# LionIRVT-PMP40182_Control.net
KiCad netlist of a schematic drawn in Altium Designer
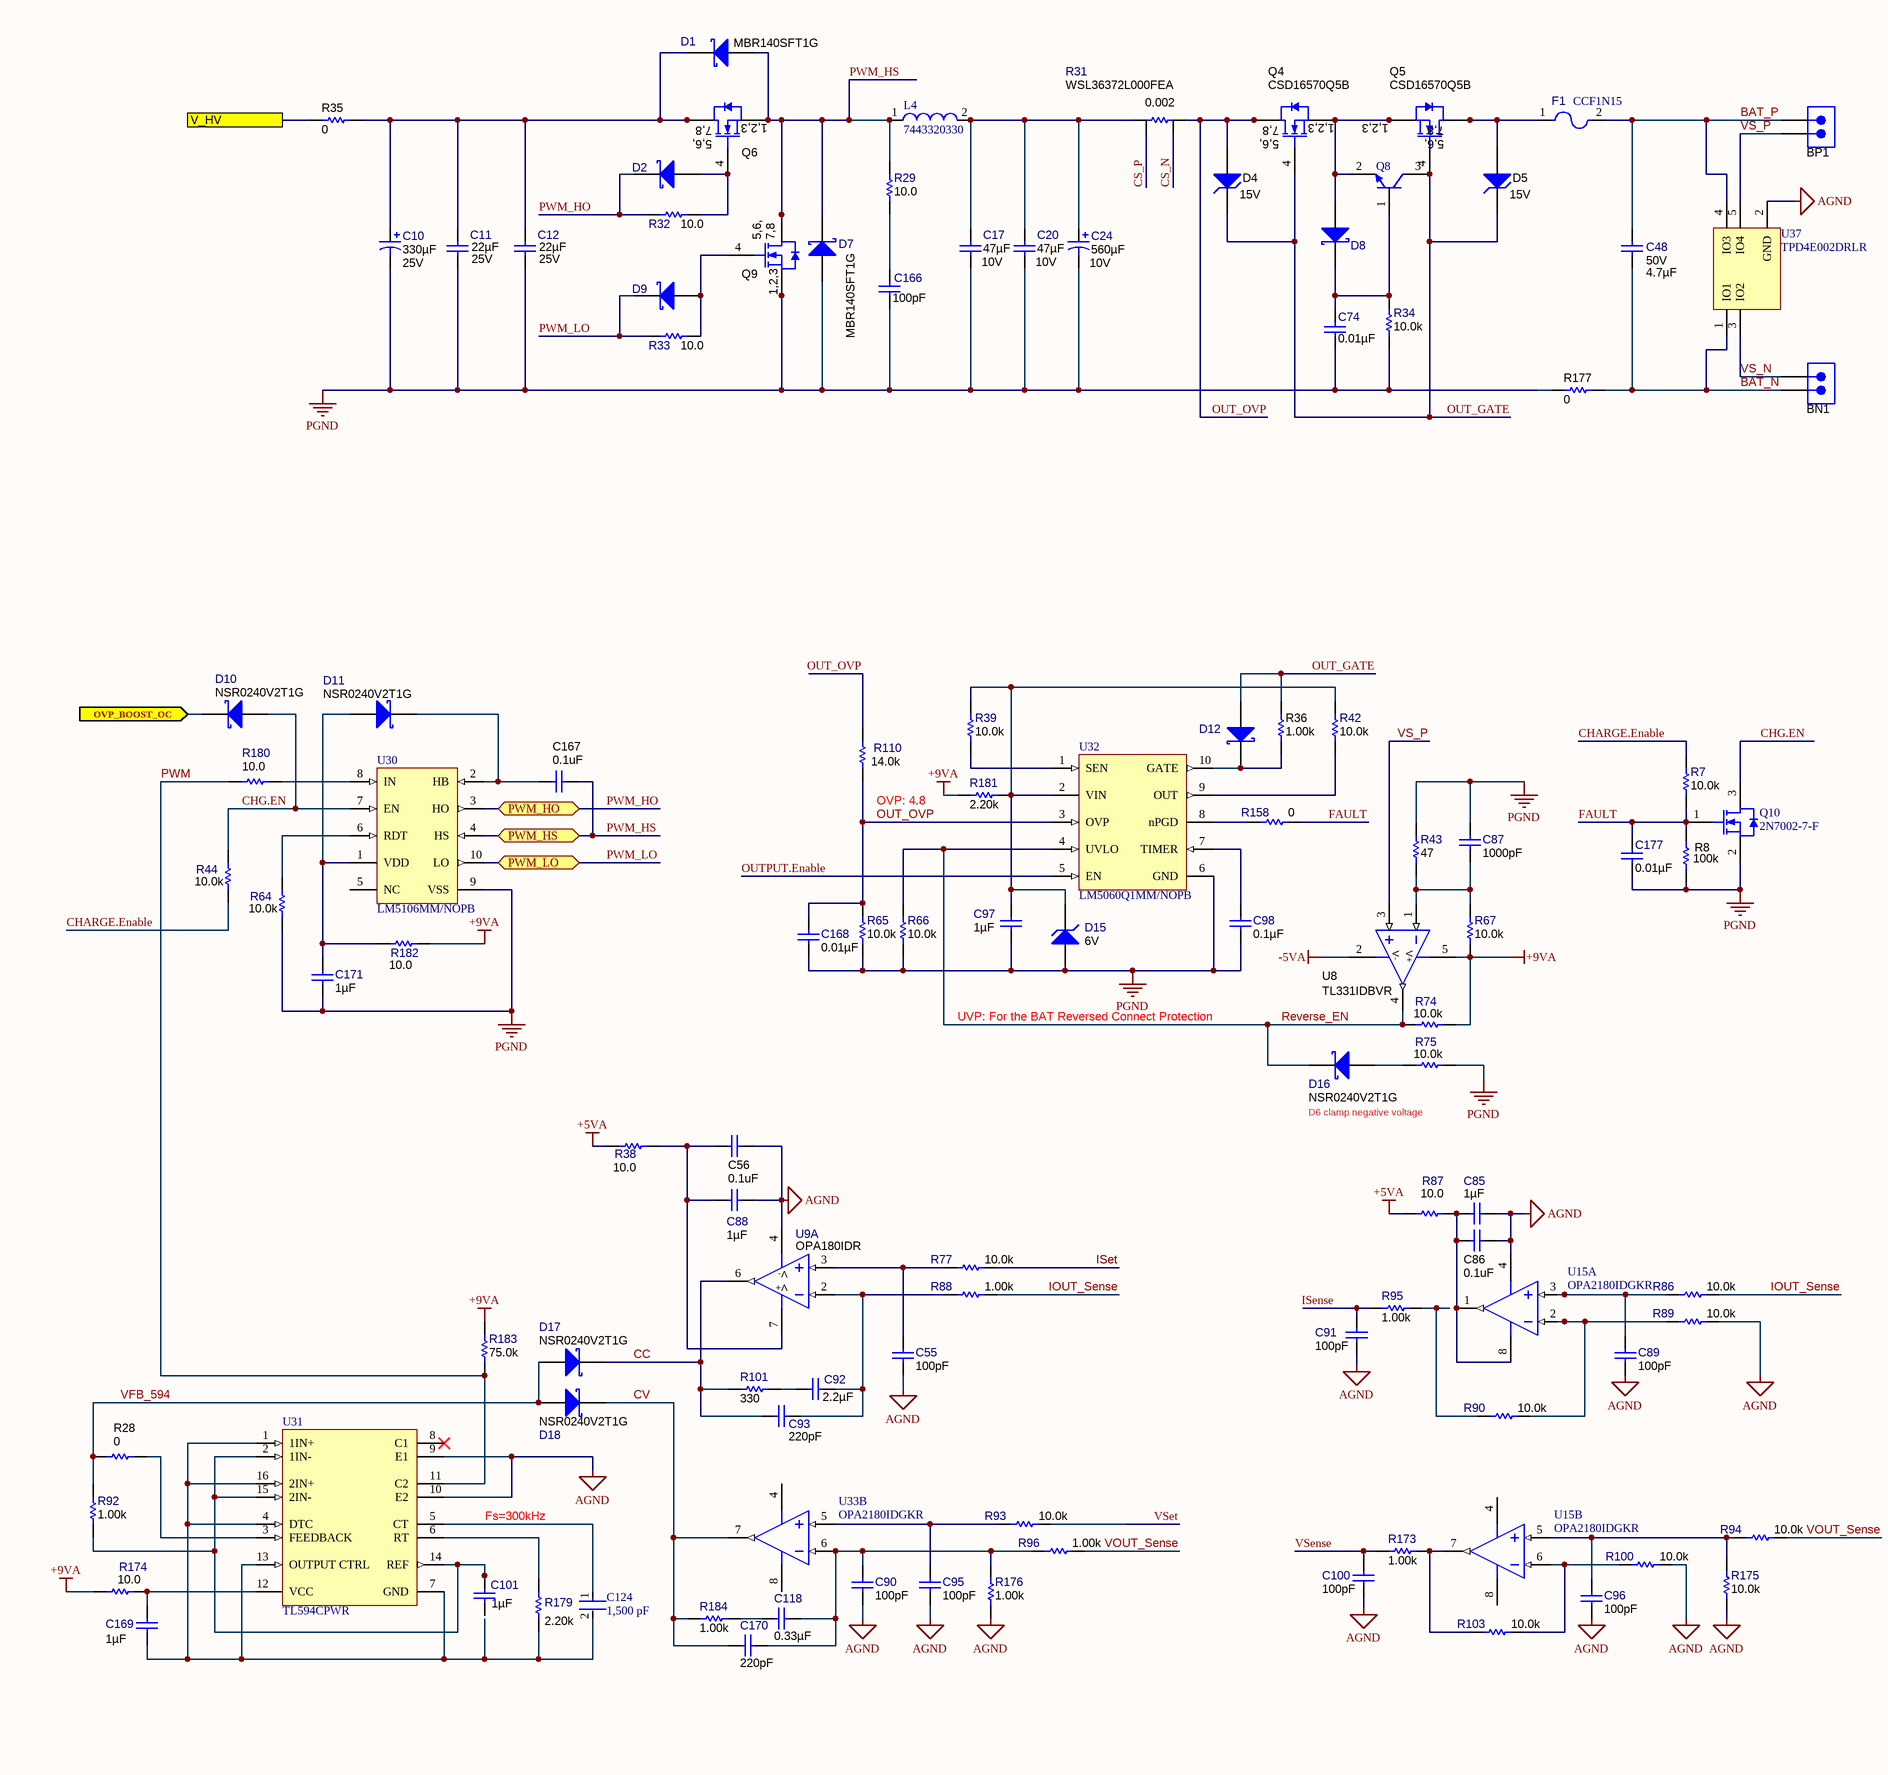
[diagram p0: LionIRVT-PMP40182.Control.SchDoc, left]
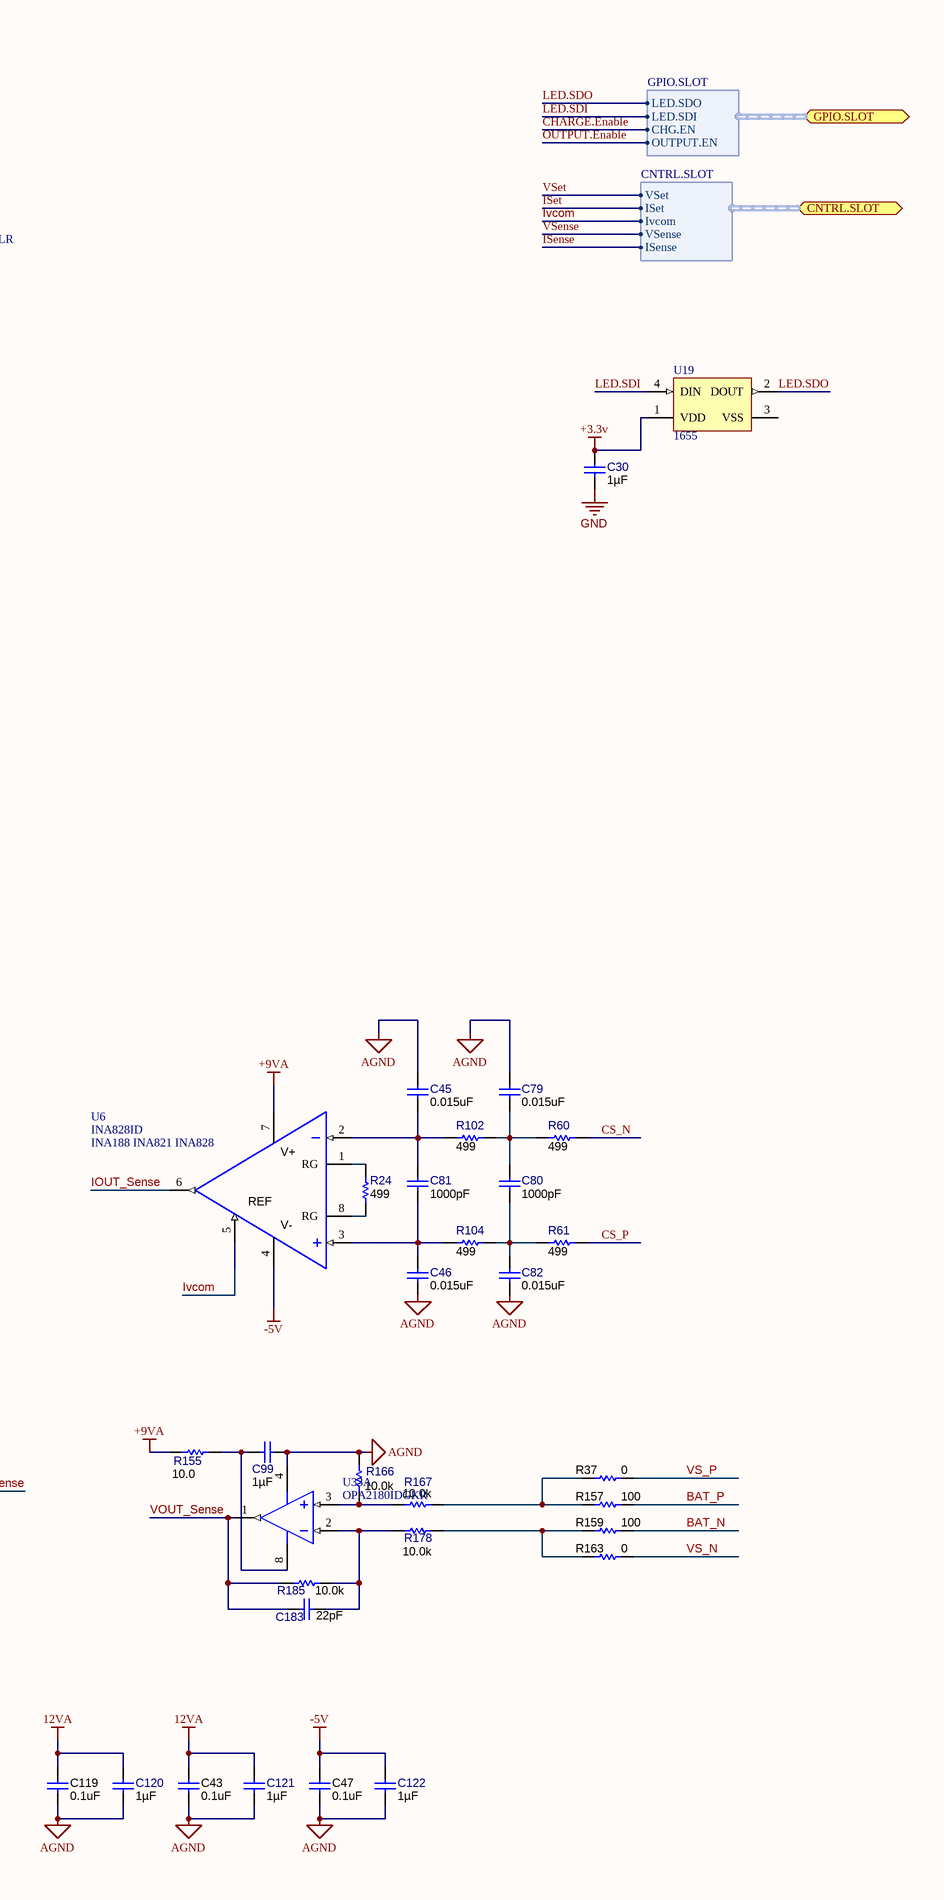
[diagram p1: LionIRVT-PMP40182.Control.SchDoc, right]

(export (version "E")
  (design (tool "Eeschema 10.0.6"))
  (components
    (comp (ref "BN1")
      (value "ED555/2DS")
      (footprint "TERM_BLK_ED555-2DS")
      (description "Terminal Block, 6A, 3.5mm Pitch, 2-Pos, TH")
      (fields
        (field (name "MANUFACTURER") "On-Shore Technology")
        (field (name "SYMBOLCREATOR") "a0412235")
        (field (name "PUBLISHER") "Texas Instruments")
      )
      (libsource (lib "PWR578A") (part "ED555/2DS"))
    )
    (comp (ref "BP1")
      (value "ED555/2DS")
      (footprint "TERM_BLK_ED555-2DS")
      (description "Terminal Block, 6A, 3.5mm Pitch, 2-Pos, TH")
      (fields
        (field (name "MANUFACTURER") "On-Shore Technology")
        (field (name "SYMBOLCREATOR") "a0412235")
        (field (name "PUBLISHER") "Texas Instruments")
      )
      (libsource (lib "PWR578A") (part "ED555/2DS"))
    )
    (comp (ref "C10")
      (value "25SVPF330M")
      (footprint "CAPSMT_62_F12")
      (fields
        (field (name "VALUEDISPLAYED") "330µF")
        (field (name "MANUFACTURER") "Panasonic")
        (field (name "VALUE2") "25V")
        (field (name "PUBLISHER") "Texas Instruments")
      )
      (libsource (lib "PMP40182") (part "25SVPF330M"))
    )
    (comp (ref "C11")
      (value "GRM32ER71E226KE15L")
      (footprint "1210_270")
      (description "CAP, CERM, 22 µF, 25 V, +/- 10%, X7R, 1210")
      (fields
        (field (name "VALUEDISPLAYED") "22µF")
        (field (name "MANUFACTURER") "MuRata")
        (field (name "VALUE2") "25V")
        (field (name "PUBLISHER") "Texas Instruments")
      )
      (libsource (lib "Capacitor_Ceramic") (part "GRM32ER71E226KE15L"))
    )
    (comp (ref "C12")
      (value "GRM32ER71E226KE15L")
      (footprint "1210_270")
      (description "CAP, CERM, 22 µF, 25 V, +/- 10%, X7R, 1210")
      (fields
        (field (name "VALUEDISPLAYED") "22µF")
        (field (name "MANUFACTURER") "MuRata")
        (field (name "VALUE2") "25V")
        (field (name "PUBLISHER") "Texas Instruments")
      )
      (libsource (lib "Capacitor_Ceramic") (part "GRM32ER71E226KE15L"))
    )
    (comp (ref "C17")
      (value "GRM32ER71A476ME15L")
      (footprint "1210_270")
      (description "CAP, CERM, 47 µF, 10 V, +/- 20%, X7R, 1210")
      (fields
        (field (name "VALUEDISPLAYED") "47µF")
        (field (name "MANUFACTURER") "MuRata")
        (field (name "VALUE2") "10V")
        (field (name "PUBLISHER") "Texas Instruments")
      )
      (libsource (lib "Capacitor_Ceramic") (part "GRM32ER71A476ME15L"))
    )
    (comp (ref "C20")
      (value "GRM32ER71A476ME15L")
      (footprint "1210_270")
      (description "CAP, CERM, 47 µF, 10 V, +/- 20%, X7R, 1210")
      (fields
        (field (name "VALUEDISPLAYED") "47µF")
        (field (name "MANUFACTURER") "MuRata")
        (field (name "VALUE2") "10V")
        (field (name "PUBLISHER") "Texas Instruments")
      )
      (libsource (lib "Capacitor_Ceramic") (part "GRM32ER71A476ME15L"))
    )
    (comp (ref "C24")
      (value "10SVP560M")
      (footprint "SM_RADIAL_10AMM")
      (description "CAP, Aluminum Polymer, 560 µF, 10 V, +/- 20%, 0.013 ohm, 10x10.3 SMD")
      (fields
        (field (name "VALUEDISPLAYED") "560µF")
        (field (name "MANUFACTURER") "Panasonic")
        (field (name "VALUE2") "10V")
        (field (name "PUBLISHER") "Texas Instruments")
      )
      (libsource (lib "Capacitor_Other") (part "10SVP560M"))
    )
    (comp (ref "C30")
      (value "C0603C105K3RACTU")
      (footprint "0603C")
      (description "CAP, CERM, 1 µF, 25 V, +/- 10%, X7R, 0603")
      (fields
        (field (name "VALUEDISPLAYED") "1µF")
        (field (name "MANUFACTURER") "Kemet")
        (field (name "PUBLISHER") "Texas Instruments")
      )
      (libsource (lib "Capacitor_Ceramic") (part "C0603C105K3RACTU"))
    )
    (comp (ref "C43")
      (value "Capacitor")
      (footprint "0603C")
      (description "CAP, CERM, 0.1 uF, 25 V, +/- 5%, X7R, 0603")
      (fields
        (field (name "PARTNUMBER") "06033C104JAT2A")
        (field (name "VALUEDISPLAYED") "0.1uF")
        (field (name "MANUFACTURER") "AVX")
        (field (name "PUBLISHER") "Texas Instruments")
      )
      (libsource (lib "PMP40182") (part "CMP-0006752-5"))
    )
    (comp (ref "C45")
      (value "Capacitor")
      (footprint "0603C")
      (description "CAP, CERM, 0.015 uF, 16 V, +/- 10%, X7R, 0603")
      (fields
        (field (name "PARTNUMBER") "GRM188R71C153KA01D")
        (field (name "VALUEDISPLAYED") "0.015uF")
        (field (name "MANUFACTURER") "MuRata")
        (field (name "PUBLISHER") "Texas Instruments")
      )
      (libsource (lib "Miscellaneous Devices") (part "CMP-0007383-5"))
    )
    (comp (ref "C46")
      (value "Capacitor")
      (footprint "0603C")
      (description "CAP, CERM, 0.015 uF, 16 V, +/- 10%, X7R, 0603")
      (fields
        (field (name "PARTNUMBER") "GRM188R71C153KA01D")
        (field (name "VALUEDISPLAYED") "0.015uF")
        (field (name "MANUFACTURER") "MuRata")
        (field (name "PUBLISHER") "Texas Instruments")
      )
      (libsource (lib "Miscellaneous Devices") (part "CMP-0007383-5"))
    )
    (comp (ref "C47")
      (value "Capacitor")
      (footprint "0603C")
      (description "CAP, CERM, 0.1 uF, 25 V, +/- 5%, X7R, 0603")
      (fields
        (field (name "PARTNUMBER") "06033C104JAT2A")
        (field (name "VALUEDISPLAYED") "0.1uF")
        (field (name "MANUFACTURER") "AVX")
        (field (name "PUBLISHER") "Texas Instruments")
      )
      (libsource (lib "PMP40182") (part "CMP-0006752-5"))
    )
    (comp (ref "C48")
      (value "GRM319R61H475KA12")
      (footprint "1206L")
      (description "CAP, CERM, 4.7 µF, 50 V, +/- 10%, X5R, 1206")
      (fields
        (field (name "VALUEDISPLAYED") "4.7µF")
        (field (name "MANUFACTURER") "MuRata")
        (field (name "VALUE2") "50V")
        (field (name "PUBLISHER") "Texas Instruments")
      )
      (libsource (lib "Capacitor_Ceramic") (part "GRM319R61H475KA12"))
    )
    (comp (ref "C55")
      (value "GRM1885C1H101JA01D")
      (footprint "0603C")
      (description "CAP, CERM, 100 pF, 50 V, +/- 5%, C0G/NP0, 0603")
      (fields
        (field (name "VALUEDISPLAYED") "100pF")
        (field (name "MANUFACTURER") "MuRata")
        (field (name "PUBLISHER") "Texas Instruments")
      )
      (libsource (lib "Capacitor_Ceramic") (part "GRM1885C1H101JA01D"))
    )
    (comp (ref "C56")
      (value "Capacitor")
      (footprint "0603C")
      (description "CAP, CERM, 0.1 uF, 25 V, +/- 5%, X7R, 0603")
      (fields
        (field (name "PARTNUMBER") "06033C104JAT2A")
        (field (name "VALUEDISPLAYED") "0.1uF")
        (field (name "MANUFACTURER") "AVX")
        (field (name "PUBLISHER") "Texas Instruments")
      )
      (libsource (lib "SV601272A") (part "CMP-0006752-5"))
    )
    (comp (ref "C74")
      (value "GRM1885C1H103JA01D")
      (footprint "0603C")
      (description "CAP, CERM, 0.01 µF, 50 V, +/- 5%, C0G/NP0, 0603")
      (fields
        (field (name "VALUEDISPLAYED") "0.01µF")
        (field (name "MANUFACTURER") "MuRata")
        (field (name "PUBLISHER") "Texas Instruments")
      )
      (libsource (lib "PMP40182") (part "GRM1885C1H103JA01D"))
    )
    (comp (ref "C79")
      (value "Capacitor")
      (footprint "0603C")
      (description "CAP, CERM, 0.015 uF, 16 V, +/- 10%, X7R, 0603")
      (fields
        (field (name "PARTNUMBER") "GRM188R71C153KA01D")
        (field (name "VALUEDISPLAYED") "0.015uF")
        (field (name "MANUFACTURER") "MuRata")
        (field (name "PUBLISHER") "Texas Instruments")
      )
      (libsource (lib "Miscellaneous Devices") (part "CMP-0007383-5"))
    )
    (comp (ref "C80")
      (value "Capacitor")
      (footprint "0603C")
      (description "CAP, CERM, 0.015 uF, 16 V, +/- 10%, X7R, 0603")
      (fields
        (field (name "PARTNUMBER") "GRM188R71C153KA01D")
        (field (name "VALUEDISPLAYED") "1000pF")
        (field (name "MANUFACTURER") "MuRata")
        (field (name "PUBLISHER") "Texas Instruments")
      )
      (libsource (lib "Miscellaneous Devices") (part "CMP-0007383-5"))
    )
    (comp (ref "C81")
      (value "Capacitor")
      (footprint "0603C")
      (description "CAP, CERM, 0.015 uF, 16 V, +/- 10%, X7R, 0603")
      (fields
        (field (name "PARTNUMBER") "GRM188R71C153KA01D")
        (field (name "VALUEDISPLAYED") "1000pF")
        (field (name "MANUFACTURER") "MuRata")
        (field (name "PUBLISHER") "Texas Instruments")
      )
      (libsource (lib "Miscellaneous Devices") (part "CMP-0007383-5"))
    )
    (comp (ref "C82")
      (value "Capacitor")
      (footprint "0603C")
      (description "CAP, CERM, 0.015 uF, 16 V, +/- 10%, X7R, 0603")
      (fields
        (field (name "PARTNUMBER") "GRM188R71C153KA01D")
        (field (name "VALUEDISPLAYED") "0.015uF")
        (field (name "MANUFACTURER") "MuRata")
        (field (name "PUBLISHER") "Texas Instruments")
      )
      (libsource (lib "Miscellaneous Devices") (part "CMP-0007383-5"))
    )
    (comp (ref "C85")
      (value "C0603C105K3RACTU")
      (footprint "0603C")
      (description "CAP, CERM, 1 µF, 25 V, +/- 10%, X7R, 0603")
      (fields
        (field (name "VALUEDISPLAYED") "1µF")
        (field (name "MANUFACTURER") "Kemet")
        (field (name "PUBLISHER") "Texas Instruments")
      )
      (libsource (lib "Capacitor_Ceramic") (part "C0603C105K3RACTU"))
    )
    (comp (ref "C86")
      (value "Capacitor")
      (footprint "0603C")
      (description "CAP, CERM, 0.1 uF, 25 V, +/- 5%, X7R, 0603")
      (fields
        (field (name "PARTNUMBER") "06033C104JAT2A")
        (field (name "VALUEDISPLAYED") "0.1uF")
        (field (name "MANUFACTURER") "AVX")
        (field (name "PUBLISHER") "Texas Instruments")
      )
      (libsource (lib "SV601272A") (part "CMP-0006752-5"))
    )
    (comp (ref "C87")
      (value "GRM1885C1H102JA01D")
      (footprint "0603C")
      (description "CAP, CERM, 1000 pF, 50 V, +/- 5%, C0G/NP0, 0603")
      (fields
        (field (name "VALUEDISPLAYED") "1000pF")
        (field (name "MANUFACTURER") "MuRata")
        (field (name "PUBLISHER") "Texas Instruments")
      )
      (libsource (lib "Capacitor_Ceramic") (part "GRM1885C1H102JA01D"))
    )
    (comp (ref "C88")
      (value "C0603C105K3RACTU")
      (footprint "0603C")
      (description "CAP, CERM, 1 µF, 25 V, +/- 10%, X7R, 0603")
      (fields
        (field (name "VALUEDISPLAYED") "1µF")
        (field (name "MANUFACTURER") "Kemet")
        (field (name "PUBLISHER") "Texas Instruments")
      )
      (libsource (lib "Capacitor_Ceramic") (part "C0603C105K3RACTU"))
    )
    (comp (ref "C89")
      (value "GRM1885C1H101JA01D")
      (footprint "0603C")
      (description "CAP, CERM, 100 pF, 50 V, +/- 5%, C0G/NP0, 0603")
      (fields
        (field (name "VALUEDISPLAYED") "100pF")
        (field (name "MANUFACTURER") "MuRata")
        (field (name "PUBLISHER") "Texas Instruments")
      )
      (libsource (lib "Capacitor_Ceramic") (part "GRM1885C1H101JA01D"))
    )
    (comp (ref "C90")
      (value "GRM1885C1H101JA01D")
      (footprint "0603C")
      (description "CAP, CERM, 100 pF, 50 V, +/- 5%, C0G/NP0, 0603")
      (fields
        (field (name "VALUEDISPLAYED") "100pF")
        (field (name "MANUFACTURER") "MuRata")
        (field (name "PUBLISHER") "Texas Instruments")
      )
      (libsource (lib "Capacitor_Ceramic") (part "GRM1885C1H101JA01D"))
    )
    (comp (ref "C91")
      (value "GRM1885C1H101JA01D")
      (footprint "0603C")
      (description "CAP, CERM, 100 pF, 50 V, +/- 5%, C0G/NP0, 0603")
      (fields
        (field (name "VALUEDISPLAYED") "100pF")
        (field (name "MANUFACTURER") "MuRata")
        (field (name "PUBLISHER") "Texas Instruments")
      )
      (libsource (lib "Capacitor_Ceramic") (part "GRM1885C1H101JA01D"))
    )
    (comp (ref "C92")
      (value "GRM188R71A225KE15D")
      (footprint "0603C")
      (description "CAP, CERM, 2.2 µF, 10 V, +/- 10%, X7R, 0603")
      (fields
        (field (name "VALUEDISPLAYED") "2.2µF")
        (field (name "MANUFACTURER") "MuRata")
        (field (name "PUBLISHER") "Texas Instruments")
      )
      (libsource (lib "Capacitor_Ceramic") (part "GRM188R71A225KE15D"))
    )
    (comp (ref "C93")
      (value "GRM1885C1H221JA01D")
      (footprint "0603C")
      (description "CAP, CERM, 220 pF, 50 V, +/- 5%, C0G/NP0, 0603")
      (fields
        (field (name "VALUEDISPLAYED") "220pF")
        (field (name "MANUFACTURER") "MuRata")
        (field (name "PUBLISHER") "Texas Instruments")
      )
      (libsource (lib "Capacitor_Ceramic") (part "GRM1885C1H221JA01D"))
    )
    (comp (ref "C95")
      (value "GRM1885C1H101JA01D")
      (footprint "0603C")
      (description "CAP, CERM, 100 pF, 50 V, +/- 5%, C0G/NP0, 0603")
      (fields
        (field (name "VALUEDISPLAYED") "100pF")
        (field (name "MANUFACTURER") "MuRata")
        (field (name "PUBLISHER") "Texas Instruments")
      )
      (libsource (lib "Capacitor_Ceramic") (part "GRM1885C1H101JA01D"))
    )
    (comp (ref "C96")
      (value "GRM1885C1H101JA01D")
      (footprint "0603C")
      (description "CAP, CERM, 100 pF, 50 V, +/- 5%, C0G/NP0, 0603")
      (fields
        (field (name "VALUEDISPLAYED") "100pF")
        (field (name "MANUFACTURER") "MuRata")
        (field (name "PUBLISHER") "Texas Instruments")
      )
      (libsource (lib "Capacitor_Ceramic") (part "GRM1885C1H101JA01D"))
    )
    (comp (ref "C97")
      (value "C0603C105K3RACTU")
      (footprint "0603C")
      (description "CAP, CERM, 1 µF, 25 V, +/- 10%, X7R, 0603")
      (fields
        (field (name "VALUEDISPLAYED") "1µF")
        (field (name "MANUFACTURER") "Kemet")
        (field (name "PUBLISHER") "Texas Instruments")
      )
      (libsource (lib "Capacitor_Ceramic") (part "C0603C105K3RACTU"))
    )
    (comp (ref "C98")
      (value "C0603C104J3RACTU")
      (footprint "0603C")
      (description "CAP, CERM, 0.1 µF, 25 V, +/- 5%, X7R, 0603")
      (fields
        (field (name "VALUEDISPLAYED") "0.1µF")
        (field (name "MANUFACTURER") "Kemet")
        (field (name "PUBLISHER") "Texas Instruments")
      )
      (libsource (lib "Capacitor_Ceramic") (part "C0603C104J3RACTU"))
    )
    (comp (ref "C99")
      (value "C0603C105K3RACTU")
      (footprint "0603C")
      (description "CAP, CERM, 1 µF, 25 V, +/- 10%, X7R, 0603")
      (fields
        (field (name "VALUEDISPLAYED") "1µF")
        (field (name "MANUFACTURER") "Kemet")
        (field (name "PUBLISHER") "Texas Instruments")
      )
      (libsource (lib "PMP40182") (part "C0603C105K3RACTU"))
    )
    (comp (ref "C100")
      (value "GRM1885C1H101JA01D")
      (footprint "0603C")
      (description "CAP, CERM, 100 pF, 50 V, +/- 5%, C0G/NP0, 0603")
      (fields
        (field (name "VALUEDISPLAYED") "100pF")
        (field (name "MANUFACTURER") "MuRata")
        (field (name "PUBLISHER") "Texas Instruments")
      )
      (libsource (lib "Capacitor_Ceramic") (part "GRM1885C1H101JA01D"))
    )
    (comp (ref "C101")
      (value "C0603C105K3RACTU")
      (footprint "0603C")
      (description "CAP, CERM, 1 µF, 25 V, +/- 10%, X7R, 0603")
      (fields
        (field (name "VALUEDISPLAYED") "1µF")
        (field (name "MANUFACTURER") "Kemet")
        (field (name "PUBLISHER") "Texas Instruments")
      )
      (libsource (lib "Capacitor_Ceramic") (part "C0603C105K3RACTU"))
    )
    (comp (ref "C118")
      (value "GRM188R71A334KA61D")
      (footprint "0603C")
      (description "CAP, CERM, 0.33 µF, 10 V, +/- 10%, X7R, 0603")
      (fields
        (field (name "VALUEDISPLAYED") "0.33µF")
        (field (name "MANUFACTURER") "MuRata")
        (field (name "PUBLISHER") "Texas Instruments")
      )
      (libsource (lib "Capacitor_Ceramic") (part "GRM188R71A334KA61D"))
    )
    (comp (ref "C119")
      (value "Capacitor")
      (footprint "0603C")
      (description "CAP, CERM, 0.1 uF, 25 V, +/- 5%, X7R, 0603")
      (fields
        (field (name "PARTNUMBER") "06033C104JAT2A")
        (field (name "VALUEDISPLAYED") "0.1uF")
        (field (name "MANUFACTURER") "AVX")
        (field (name "PUBLISHER") "Texas Instruments")
      )
      (libsource (lib "PMP40182") (part "CMP-0006752-5"))
    )
    (comp (ref "C120")
      (value "C0603C105K3RACTU")
      (footprint "0603C")
      (description "CAP, CERM, 1 µF, 25 V, +/- 10%, X7R, 0603")
      (fields
        (field (name "VALUEDISPLAYED") "1µF")
        (field (name "MANUFACTURER") "Kemet")
        (field (name "PUBLISHER") "Texas Instruments")
      )
      (libsource (lib "PMP40182") (part "C0603C105K3RACTU"))
    )
    (comp (ref "C121")
      (value "C0603C105K3RACTU")
      (footprint "0603C")
      (description "CAP, CERM, 1 µF, 25 V, +/- 10%, X7R, 0603")
      (fields
        (field (name "VALUEDISPLAYED") "1µF")
        (field (name "MANUFACTURER") "Kemet")
        (field (name "PUBLISHER") "Texas Instruments")
      )
      (libsource (lib "PMP40182") (part "C0603C105K3RACTU"))
    )
    (comp (ref "C122")
      (value "C0603C105K3RACTU")
      (footprint "0603C")
      (description "CAP, CERM, 1 µF, 25 V, +/- 10%, X7R, 0603")
      (fields
        (field (name "VALUEDISPLAYED") "1µF")
        (field (name "MANUFACTURER") "Kemet")
        (field (name "PUBLISHER") "Texas Instruments")
      )
      (libsource (lib "PMP40182") (part "C0603C105K3RACTU"))
    )
    (comp (ref "C124")
      (value "C0603C152J1GACTU")
      (footprint "FP-C0603C-CF-MFG")
      (description "CAP CER 1500PF 100V NP0 0603")
      (fields
        (field (name "CAPACITANCE") "1,500 pF")
        (field (name "OCTOPART") "https://octopart.com/c0603c152j1gactu-kemet-12793172")
        (field (name "TOLERANCE") "0.05")
      )
      (libsource (lib "Altium Content Vault") (part "b4654b650e69147ec39a6b967a45e02"))
    )
    (comp (ref "C166")
      (value "GRM1885C1H101JA01D")
      (footprint "0603C")
      (description "CAP, CERM, 100 pF, 50 V, +/- 5%, C0G/NP0, 0603")
      (fields
        (field (name "VALUEDISPLAYED") "100pF")
        (field (name "MANUFACTURER") "MuRata")
        (field (name "PUBLISHER") "Texas Instruments")
      )
      (libsource (lib "Capacitor_Ceramic") (part "GRM1885C1H101JA01D"))
    )
    (comp (ref "C167")
      (value "Capacitor")
      (footprint "0603C")
      (description "CAP, CERM, 0.1 uF, 25 V, +/- 5%, X7R, 0603")
      (fields
        (field (name "PARTNUMBER") "06033C104JAT2A")
        (field (name "VALUEDISPLAYED") "0.1uF")
        (field (name "MANUFACTURER") "AVX")
        (field (name "PUBLISHER") "Texas Instruments")
      )
      (libsource (lib "SV601272A") (part "CMP-0006752-5"))
    )
    (comp (ref "C168")
      (value "GRM1885C1H103JA01D")
      (footprint "0603C")
      (description "CAP, CERM, 0.01 µF, 50 V, +/- 5%, C0G/NP0, 0603")
      (fields
        (field (name "VALUEDISPLAYED") "0.01µF")
        (field (name "MANUFACTURER") "MuRata")
        (field (name "PUBLISHER") "Texas Instruments")
      )
      (libsource (lib "Capacitor_Ceramic") (part "GRM1885C1H103JA01D"))
    )
    (comp (ref "C169")
      (value "C0603C105K3RACTU")
      (footprint "0603C")
      (description "CAP, CERM, 1 µF, 25 V, +/- 10%, X7R, 0603")
      (fields
        (field (name "VALUEDISPLAYED") "1µF")
        (field (name "MANUFACTURER") "Kemet")
        (field (name "PUBLISHER") "Texas Instruments")
      )
      (libsource (lib "Capacitor_Ceramic") (part "C0603C105K3RACTU"))
    )
    (comp (ref "C170")
      (value "GRM1885C1H221JA01D")
      (footprint "0603C")
      (description "CAP, CERM, 220 pF, 50 V, +/- 5%, C0G/NP0, 0603")
      (fields
        (field (name "VALUEDISPLAYED") "220pF")
        (field (name "MANUFACTURER") "MuRata")
        (field (name "PUBLISHER") "Texas Instruments")
      )
      (libsource (lib "Capacitor_Ceramic") (part "GRM1885C1H221JA01D"))
    )
    (comp (ref "C171")
      (value "C0603C105K3RACTU")
      (footprint "0603C")
      (description "CAP, CERM, 1 µF, 25 V, +/- 10%, X7R, 0603")
      (fields
        (field (name "VALUEDISPLAYED") "1µF")
        (field (name "MANUFACTURER") "Kemet")
        (field (name "PUBLISHER") "Texas Instruments")
      )
      (libsource (lib "Capacitor_Ceramic") (part "C0603C105K3RACTU"))
    )
    (comp (ref "C177")
      (value "GRM1885C1H103JA01D")
      (footprint "0603C")
      (description "CAP, CERM, 0.01 µF, 50 V, +/- 5%, C0G/NP0, 0603")
      (fields
        (field (name "VALUEDISPLAYED") "0.01µF")
        (field (name "MANUFACTURER") "MuRata")
        (field (name "PUBLISHER") "Texas Instruments")
      )
      (libsource (lib "Capacitor_Ceramic") (part "GRM1885C1H103JA01D"))
    )
    (comp (ref "C183")
      (value "C0603C220J5GACTU")
      (footprint "0603C")
      (description "CAP, CERM, 22 pF, 50 V, +/- 5%, C0G/NP0, 0603")
      (fields
        (field (name "VALUEDISPLAYED") "22pF")
        (field (name "MANUFACTURER") "Kemet")
        (field (name "PUBLISHER") "Texas Instruments")
      )
      (libsource (lib "PMP40182") (part "C0603C220J5GACTU"))
    )
    (comp (ref "D1")
      (value "MBR140SFT1G")
      (footprint "SOD-123FL")
      (description "Diode, Schottky, 40 V, 1 A, SOD-123FL")
      (fields (field (name "MANUFACTURER") "ON Semiconductor") (field (name "PUBLISHER") "Texas Instruments"))
      (libsource (lib "Diode") (part "MBR140SFT1G"))
    )
    (comp (ref "D2")
      (value "NSR0240V2T1G")
      (footprint "SOD-523")
      (description "Diode, Schottky, 40V, 0.25A, SOD-523")
      (fields (field (name "MANUFACTURER") "ON Semiconductor") (field (name "PUBLISHER") "Texas Instruments"))
      (libsource (lib "Diode") (part "NSR0240V2T1G"))
    )
    (comp (ref "D4")
      (value "15V")
      (footprint "sod-323")
      (description "Diode, Zener, 15 V, 200 mW, SOD-323")
      (fields
        (field (name "PARTNUMBER") "MMSZ5245BS-7-F")
        (field (name "MANUFACTURER") "Diodes Inc.")
        (field (name "SYMBOLCREATOR") "a0412235")
        (field (name "PUBLISHER") "Texas Instruments")
      )
      (libsource (lib "ZenerDiodes") (part "MMSZ5245BS-7-F"))
    )
    (comp (ref "D5")
      (value "15V")
      (footprint "sod-323")
      (description "Diode, Zener, 15 V, 200 mW, SOD-323")
      (fields
        (field (name "PARTNUMBER") "MMSZ5245BS-7-F")
        (field (name "MANUFACTURER") "Diodes Inc.")
        (field (name "SYMBOLCREATOR") "a0412235")
        (field (name "PUBLISHER") "Texas Instruments")
      )
      (libsource (lib "ZenerDiodes") (part "MMSZ5245BS-7-F"))
    )
    (comp (ref "D7")
      (value "MBR140SFT1G")
      (footprint "SOD-123FL")
      (description "Diode, Schottky, 40 V, 1 A, SOD-123FL")
      (fields (field (name "MANUFACTURER") "ON Semiconductor") (field (name "PUBLISHER") "Texas Instruments"))
      (libsource (lib "Diode") (part "MBR140SFT1G"))
    )
    (comp (ref "D8")
      (value "NSR0240V2T1G")
      (footprint "SOD-523")
      (description "Diode, Schottky, 40V, 0.25A, SOD-523")
      (fields (field (name "MANUFACTURER") "ON Semiconductor") (field (name "PUBLISHER") "Texas Instruments"))
      (libsource (lib "Diode") (part "NSR0240V2T1G"))
    )
    (comp (ref "D9")
      (value "NSR0240V2T1G")
      (footprint "SOD-523")
      (description "Diode, Schottky, 40V, 0.25A, SOD-523")
      (fields (field (name "MANUFACTURER") "ON Semiconductor") (field (name "PUBLISHER") "Texas Instruments"))
      (libsource (lib "Diode") (part "NSR0240V2T1G"))
    )
    (comp (ref "D10")
      (value "NSR0240V2T1G")
      (footprint "SOD-523")
      (description "Diode, Schottky, 40V, 0.25A, SOD-523")
      (fields (field (name "MANUFACTURER") "ON Semiconductor") (field (name "PUBLISHER") "Texas Instruments"))
      (libsource (lib "Diode") (part "NSR0240V2T1G"))
    )
    (comp (ref "D11")
      (value "NSR0240V2T1G")
      (footprint "SOD-523")
      (description "Diode, Schottky, 40V, 0.25A, SOD-523")
      (fields (field (name "MANUFACTURER") "ON Semiconductor") (field (name "PUBLISHER") "Texas Instruments"))
      (libsource (lib "Diode") (part "NSR0240V2T1G"))
    )
    (comp (ref "D12")
      (value "NSR0240V2T1G")
      (footprint "SOD-523")
      (description "Diode, Schottky, 40V, 0.25A, SOD-523")
      (fields (field (name "MANUFACTURER") "ON Semiconductor") (field (name "PUBLISHER") "Texas Instruments"))
      (libsource (lib "Diode") (part "NSR0240V2T1G"))
    )
    (comp (ref "D15")
      (value "6V")
      (footprint "sod-323")
      (description "Diode, Zener, 6 V, 200 mW, SOD-323")
      (fields
        (field (name "PARTNUMBER") "MMSZ5233BS-7-F")
        (field (name "MANUFACTURER") "Diodes Inc.")
        (field (name "PUBLISHER") "Texas Instruments")
        (field (name "SYMBOLCREATOR") "a0412235")
      )
      (libsource (lib "ZenerDiodes") (part "MMSZ5233BS-7-F"))
    )
    (comp (ref "D16")
      (value "NSR0240V2T1G")
      (footprint "SOD-523")
      (description "Diode, Schottky, 40V, 0.25A, SOD-523")
      (fields (field (name "MANUFACTURER") "ON Semiconductor") (field (name "PUBLISHER") "Texas Instruments"))
      (libsource (lib "Diode") (part "NSR0240V2T1G"))
    )
    (comp (ref "D17")
      (value "NSR0240V2T1G")
      (footprint "SOD-523")
      (description "Diode, Schottky, 40V, 0.25A, SOD-523")
      (fields (field (name "MANUFACTURER") "ON Semiconductor") (field (name "PUBLISHER") "Texas Instruments"))
      (libsource (lib "Diode") (part "NSR0240V2T1G"))
    )
    (comp (ref "D18")
      (value "NSR0240V2T1G")
      (footprint "SOD-523")
      (description "Diode, Schottky, 40V, 0.25A, SOD-523")
      (fields (field (name "MANUFACTURER") "ON Semiconductor") (field (name "PUBLISHER") "Texas Instruments"))
      (libsource (lib "Diode") (part "NSR0240V2T1G"))
    )
    (comp (ref "F1")
      (value "CCF1N15")
      (footprint "FUSE_CCF")
      (description "Fuse, Fast Acting, 50VDC, 20A")
      (fields (field (name "MANUFACTURER") "Koanet"))
      (libsource (lib "PADSlegacy_Passive") (part "FUSE_CCF1N_SERIES"))
    )
    (comp (ref "L4")
      (value "7443320330")
      (footprint "WE-HCC-1210")
      (description "SMD High Current Cube Inductor WE-HCC, L=3.30 µH")
      (libsource (lib "Altium Content Vault") (part "PAS-IND-INDUCTOR-2"))
    )
    (comp (ref "Q4")
      (value "CSD16570Q5B")
      (footprint "DNK8")
      (description "25V, N ch NexFET MOSFET™, single SON5x6, 0.82mOhm")
      (fields
        (field (name "MANUFACTURER") "Texas Instruments")
        (field (name "MANUFACTURER PART NUMBER") "CSD16570Q5BT")
      )
      (libsource (lib "PWR578A") (part "CSD16570Q5B"))
    )
    (comp (ref "Q5")
      (value "CSD16570Q5B")
      (footprint "DNK8")
      (description "25V, N ch NexFET MOSFET™, single SON5x6, 0.82mOhm")
      (fields
        (field (name "MANUFACTURER") "Texas Instruments")
        (field (name "MANUFACTURER PART NUMBER") "CSD16570Q5BT")
      )
      (libsource (lib "PWR578A") (part "CSD16570Q5B"))
    )
    (comp (ref "Q6")
      (value "CSD18502Q5B")
      (footprint "DNK8")
      (description "40V, N ch NexFET MOSFET™, single SON5x6, 2.3mOhm")
      (fields (field (name "MANUFACTURER") "Texas Instruments"))
      (libsource (lib "PWR578A") (part "CSD18502Q5B"))
    )
    (comp (ref "Q8")
      (value "MMBT2222ALT1G")
      (footprint "ONSC-SOT-23-3-318-08_V")
      (description "General Purpose Transistor, NPN Silicon, 3-Pin SOT-23, Pb-Free, Tape and Reel")
      (fields (field (name "MANUFACTURER") "On Semiconductor"))
      (libsource (lib "Altium Content Vault") (part "ONSC-NPN-B1E2C3-3"))
    )
    (comp (ref "Q9")
      (value "CSD18502Q5B")
      (footprint "DNK8")
      (description "40V, N ch NexFET MOSFET™, single SON5x6, 2.3mOhm")
      (fields (field (name "MANUFACTURER") "Texas Instruments"))
      (libsource (lib "PWR578A") (part "CSD18502Q5B"))
    )
    (comp (ref "Q10")
      (value "2N7002-7-F")
      (footprint "DIOD-SOT23-3_V")
      (fields (field (name "MANUFACTURER") "DiodesIncorporated"))
      (libsource (lib "Altium Content Vault") (part "NEMOS-GSD-3"))
    )
    (comp (ref "R7")
      (value "RC0603FR-0710KL")
      (footprint "0603R")
      (description "RES, 10.0 k, 1%, 0.1 W, 0603")
      (fields
        (field (name "VALUEDISPLAYED") "10.0k")
        (field (name "MANUFACTURER") "Yageo America")
        (field (name "PUBLISHER") "Texas Instruments")
      )
      (libsource (lib "Resistor_0603") (part "RC0603FR-0710KL"))
    )
    (comp (ref "R8")
      (value "Resistor")
      (footprint "0603R")
      (description "RES, 100 k, 1%, 0.1 W, AEC-Q200 Grade 0, 0603")
      (fields
        (field (name "PARTNUMBER") "CRCW0603100KFKEA")
        (field (name "MANUFACTURER") "Vishay-Dale")
        (field (name "VALUEDISPLAYED") "100k")
      )
      (libsource (lib "SV601272A") (part "CMP-0021990-4"))
    )
    (comp (ref "R24")
      (value "RC0603FR-07499RL")
      (footprint "0603R")
      (description "RES, 499, 1%, 0.1 W, 0603")
      (fields
        (field (name "VALUEDISPLAYED") "499")
        (field (name "MANUFACTURER") "Yageo America")
        (field (name "PUBLISHER") "Texas Instruments")
      )
      (libsource (lib "Miscellaneous Devices") (part "RC0603FR-07499RL"))
    )
    (comp (ref "R28")
      (value "Resistor")
      (footprint "0603R")
      (description "RES, 0, 5%, 0.1 W, 0603")
      (fields
        (field (name "PARTNUMBER") "ERJ-3GEY0R00V")
        (field (name "MANUFACTURER") "Panasonic")
        (field (name "VALUEDISPLAYED") "0")
        (field (name "PUBLISHER") "Texas Instruments")
      )
      (libsource (lib "PMP40182") (part "Resistor"))
    )
    (comp (ref "R29")
      (value "RC1206FR-0710RL")
      (footprint "1206L")
      (description "RES, 10.0, 1%, 0.25 W, 1206")
      (fields
        (field (name "VALUEDISPLAYED") "10.0")
        (field (name "MANUFACTURER") "Yageo America")
        (field (name "PUBLISHER") "Texas Instruments")
      )
      (libsource (lib "Resistor_1206") (part "RC1206FR-0710RL"))
    )
    (comp (ref "R31")
      (value "WSL36372L000FEA")
      (footprint "WSL3637_0.001")
      (description "RES, 0.002, 1%, 3 W, WSL3637")
      (fields
        (field (name "MANUFACTURER") "Vishay-Dale")
        (field (name "VALUEDISPLAYED") "0.002")
        (field (name "PUBLISHER") "Texas Instruments")
      )
      (libsource (lib "Resistor_OtherSMT") (part "WSL36371L000FEA"))
    )
    (comp (ref "R32")
      (value "RC0603FR-0710RL")
      (footprint "0603R")
      (description "RES, 10.0, 1%, 0.1 W, 0603")
      (fields
        (field (name "VALUEDISPLAYED") "10.0")
        (field (name "MANUFACTURER") "Yageo America")
        (field (name "PUBLISHER") "Texas Instruments")
      )
      (libsource (lib "Resistor_0603") (part "RC0603FR-0710RL"))
    )
    (comp (ref "R33")
      (value "RC0603FR-0710RL")
      (footprint "0603R")
      (description "RES, 10.0, 1%, 0.1 W, 0603")
      (fields
        (field (name "VALUEDISPLAYED") "10.0")
        (field (name "MANUFACTURER") "Yageo America")
        (field (name "PUBLISHER") "Texas Instruments")
      )
      (libsource (lib "Resistor_0603") (part "RC0603FR-0710RL"))
    )
    (comp (ref "R34")
      (value "RC0603FR-0710KL")
      (footprint "0603R")
      (description "RES, 10.0 k, 1%, 0.1 W, 0603")
      (fields
        (field (name "VALUEDISPLAYED") "10.0k")
        (field (name "MANUFACTURER") "Yageo America")
        (field (name "PUBLISHER") "Texas Instruments")
      )
      (libsource (lib "Resistor_0603") (part "RC0603FR-0710KL"))
    )
    (comp (ref "R35")
      (value "0")
      (footprint "1206")
      (description "RES, 10.0, 1%, 0.25 W, 1206")
      (fields
        (field (name "PARTNUMBER") "ERJ-8ENF10R0V")
        (field (name "MANUFACTURER") "Panasonic")
        (field (name "PUBLISHER") "Texas Instruments")
      )
      (libsource (lib "PWR578A") (part "ERJ-8ENF10R0V"))
    )
    (comp (ref "R36")
      (value "Resistor")
      (footprint "0603R")
      (description "RES, 1.00 k, 1%, 0.1 W, AEC-Q200 Grade 0, 0603")
      (fields
        (field (name "PARTNUMBER") "CRCW06031K00FKEA")
        (field (name "MANUFACTURER") "Vishay-Dale")
        (field (name "VALUEDISPLAYED") "1.00k")
      )
      (libsource (lib "PMP40182") (part "CMP-0022109-5"))
    )
    (comp (ref "R37")
      (value "Resistor")
      (footprint "0603R")
      (description "RES, 0, 5%, 0.1 W, 0603")
      (fields
        (field (name "PARTNUMBER") "ERJ-3GEY0R00V")
        (field (name "MANUFACTURER") "Panasonic")
        (field (name "VALUEDISPLAYED") "0")
        (field (name "PUBLISHER") "Texas Instruments")
      )
      (libsource (lib "PMP40182") (part "Resistor"))
    )
    (comp (ref "R38")
      (value "RC0603FR-0710RL")
      (footprint "0603R")
      (description "RES, 10.0, 1%, 0.1 W, 0603")
      (fields
        (field (name "VALUEDISPLAYED") "10.0")
        (field (name "MANUFACTURER") "Yageo America")
        (field (name "PUBLISHER") "Texas Instruments")
      )
      (libsource (lib "Resistor_0603") (part "RC0603FR-0710RL"))
    )
    (comp (ref "R39")
      (value "RC0603FR-0710KL")
      (footprint "0603R")
      (description "RES, 10.0 k, 1%, 0.1 W, 0603")
      (fields
        (field (name "VALUEDISPLAYED") "10.0k")
        (field (name "MANUFACTURER") "Yageo America")
        (field (name "PUBLISHER") "Texas Instruments")
      )
      (libsource (lib "Resistor_0603") (part "RC0603FR-0710KL"))
    )
    (comp (ref "R42")
      (value "RC0603FR-0710KL")
      (footprint "0603R")
      (description "RES, 10.0 k, 1%, 0.1 W, 0603")
      (fields
        (field (name "VALUEDISPLAYED") "10.0k")
        (field (name "MANUFACTURER") "Yageo America")
        (field (name "PUBLISHER") "Texas Instruments")
      )
      (libsource (lib "Resistor_0603") (part "RC0603FR-0710KL"))
    )
    (comp (ref "R43")
      (value "CRCW060347R0JNEA")
      (footprint "0603R")
      (description "RES, 47, 5%, 0.1 W, 0603")
      (fields
        (field (name "VALUEDISPLAYED") "47")
        (field (name "MANUFACTURER") "Vishay-Dale")
        (field (name "PUBLISHER") "Texas Instruments")
      )
      (libsource (lib "Resistor_0603") (part "CRCW060347R0JNEA"))
    )
    (comp (ref "R44")
      (value "RC0603FR-0710KL")
      (footprint "0603R")
      (description "RES, 10.0 k, 1%, 0.1 W, 0603")
      (fields
        (field (name "VALUEDISPLAYED") "10.0k")
        (field (name "MANUFACTURER") "Yageo America")
        (field (name "PUBLISHER") "Texas Instruments")
      )
      (libsource (lib "Resistor_0603") (part "RC0603FR-0710KL"))
    )
    (comp (ref "R60")
      (value "Resistor")
      (footprint "0603R")
      (description "RES, 499, 1%, 0.1 W, AEC-Q200 Grade 0, 0603")
      (fields
        (field (name "PARTNUMBER") "CRCW0603499RFKEA")
        (field (name "VALUEDISPLAYED") "499")
        (field (name "MANUFACTURER") "Vishay-Dale")
      )
      (libsource (lib "Miscellaneous Devices") (part "CMP-0022446-5"))
    )
    (comp (ref "R61")
      (value "Resistor")
      (footprint "0603R")
      (description "RES, 499, 1%, 0.1 W, AEC-Q200 Grade 0, 0603")
      (fields
        (field (name "PARTNUMBER") "CRCW0603499RFKEA")
        (field (name "VALUEDISPLAYED") "499")
        (field (name "MANUFACTURER") "Vishay-Dale")
      )
      (libsource (lib "Miscellaneous Devices") (part "CMP-0022446-5"))
    )
    (comp (ref "R64")
      (value "RC0603FR-0710KL")
      (footprint "0603R")
      (description "RES, 10.0 k, 1%, 0.1 W, 0603")
      (fields
        (field (name "VALUEDISPLAYED") "10.0k")
        (field (name "MANUFACTURER") "Yageo America")
        (field (name "PUBLISHER") "Texas Instruments")
      )
      (libsource (lib "Resistor_0603") (part "RC0603FR-0710KL"))
    )
    (comp (ref "R65")
      (value "RC0603FR-0710KL")
      (footprint "0603R")
      (description "RES, 10.0 k, 1%, 0.1 W, 0603")
      (fields
        (field (name "VALUEDISPLAYED") "10.0k")
        (field (name "MANUFACTURER") "Yageo America")
        (field (name "PUBLISHER") "Texas Instruments")
      )
      (libsource (lib "Resistor_0603") (part "RC0603FR-0710KL"))
    )
    (comp (ref "R66")
      (value "RC0603FR-0710KL")
      (footprint "0603R")
      (description "RES, 10.0 k, 1%, 0.1 W, 0603")
      (fields
        (field (name "VALUEDISPLAYED") "10.0k")
        (field (name "MANUFACTURER") "Yageo America")
        (field (name "PUBLISHER") "Texas Instruments")
      )
      (libsource (lib "Resistor_0603") (part "RC0603FR-0710KL"))
    )
    (comp (ref "R67")
      (value "RC0603FR-0710KL")
      (footprint "0603R")
      (description "RES, 10.0 k, 1%, 0.1 W, 0603")
      (fields
        (field (name "VALUEDISPLAYED") "10.0k")
        (field (name "MANUFACTURER") "Yageo America")
        (field (name "PUBLISHER") "Texas Instruments")
      )
      (libsource (lib "Resistor_0603") (part "RC0603FR-0710KL"))
    )
    (comp (ref "R74")
      (value "RC0603FR-0710KL")
      (footprint "0603R")
      (description "RES, 10.0 k, 1%, 0.1 W, 0603")
      (fields
        (field (name "VALUEDISPLAYED") "10.0k")
        (field (name "MANUFACTURER") "Yageo America")
        (field (name "PUBLISHER") "Texas Instruments")
      )
      (libsource (lib "Resistor_0603") (part "RC0603FR-0710KL"))
    )
    (comp (ref "R75")
      (value "RC0603FR-0710KL")
      (footprint "0603R")
      (description "RES, 10.0 k, 1%, 0.1 W, 0603")
      (fields
        (field (name "VALUEDISPLAYED") "10.0k")
        (field (name "MANUFACTURER") "Yageo America")
        (field (name "PUBLISHER") "Texas Instruments")
      )
      (libsource (lib "Resistor_0603") (part "RC0603FR-0710KL"))
    )
    (comp (ref "R77")
      (value "RC0603FR-0710KL")
      (footprint "0603R")
      (description "RES, 10.0 k, 1%, 0.1 W, 0603")
      (fields
        (field (name "VALUEDISPLAYED") "10.0k")
        (field (name "MANUFACTURER") "Yageo America")
        (field (name "PUBLISHER") "Texas Instruments")
      )
      (libsource (lib "Resistor_0603") (part "RC0603FR-0710KL"))
    )
    (comp (ref "R86")
      (value "RC0603FR-0710KL")
      (footprint "0603R")
      (description "RES, 10.0 k, 1%, 0.1 W, 0603")
      (fields
        (field (name "VALUEDISPLAYED") "10.0k")
        (field (name "MANUFACTURER") "Yageo America")
        (field (name "PUBLISHER") "Texas Instruments")
      )
      (libsource (lib "Resistor_0603") (part "RC0603FR-0710KL"))
    )
    (comp (ref "R87")
      (value "RC0603FR-0710RL")
      (footprint "0603R")
      (description "RES, 10.0, 1%, 0.1 W, 0603")
      (fields
        (field (name "VALUEDISPLAYED") "10.0")
        (field (name "MANUFACTURER") "Yageo America")
        (field (name "PUBLISHER") "Texas Instruments")
      )
      (libsource (lib "Resistor_0603") (part "RC0603FR-0710RL"))
    )
    (comp (ref "R88")
      (value "RC0603FR-071KL")
      (footprint "0603R")
      (description "RES, 1.00 k, 1%, 0.1 W, 0603")
      (fields
        (field (name "VALUEDISPLAYED") "1.00k")
        (field (name "MANUFACTURER") "Yageo America")
        (field (name "PUBLISHER") "Texas Instruments")
      )
      (libsource (lib "Resistor_0603") (part "RC0603FR-071KL"))
    )
    (comp (ref "R89")
      (value "RC0603FR-0710KL")
      (footprint "0603R")
      (description "RES, 10.0 k, 1%, 0.1 W, 0603")
      (fields
        (field (name "VALUEDISPLAYED") "10.0k")
        (field (name "MANUFACTURER") "Yageo America")
        (field (name "PUBLISHER") "Texas Instruments")
      )
      (libsource (lib "Resistor_0603") (part "RC0603FR-0710KL"))
    )
    (comp (ref "R90")
      (value "RC0603FR-0710KL")
      (footprint "0603R")
      (description "RES, 10.0 k, 1%, 0.1 W, 0603")
      (fields
        (field (name "VALUEDISPLAYED") "10.0k")
        (field (name "MANUFACTURER") "Yageo America")
        (field (name "PUBLISHER") "Texas Instruments")
      )
      (libsource (lib "Resistor_0603") (part "RC0603FR-0710KL"))
    )
    (comp (ref "R92")
      (value "RC0603FR-071KL")
      (footprint "0603R")
      (description "RES, 1.00 k, 1%, 0.1 W, 0603")
      (fields
        (field (name "VALUEDISPLAYED") "1.00k")
        (field (name "MANUFACTURER") "Yageo America")
        (field (name "PUBLISHER") "Texas Instruments")
      )
      (libsource (lib "Resistor_0603") (part "RC0603FR-071KL"))
    )
    (comp (ref "R93")
      (value "RC0603FR-0710KL")
      (footprint "0603R")
      (description "RES, 10.0 k, 1%, 0.1 W, 0603")
      (fields
        (field (name "VALUEDISPLAYED") "10.0k")
        (field (name "MANUFACTURER") "Yageo America")
        (field (name "PUBLISHER") "Texas Instruments")
      )
      (libsource (lib "Resistor_0603") (part "RC0603FR-0710KL"))
    )
    (comp (ref "R94")
      (value "RC0603FR-0710KL")
      (footprint "0603R")
      (description "RES, 10.0 k, 1%, 0.1 W, 0603")
      (fields
        (field (name "VALUEDISPLAYED") "10.0k")
        (field (name "MANUFACTURER") "Yageo America")
        (field (name "PUBLISHER") "Texas Instruments")
      )
      (libsource (lib "Resistor_0603") (part "RC0603FR-0710KL"))
    )
    (comp (ref "R95")
      (value "RC0603FR-071KL")
      (footprint "0603R")
      (description "RES, 1.00 k, 1%, 0.1 W, 0603")
      (fields
        (field (name "VALUEDISPLAYED") "1.00k")
        (field (name "MANUFACTURER") "Yageo America")
        (field (name "PUBLISHER") "Texas Instruments")
      )
      (libsource (lib "Resistor_0603") (part "RC0603FR-071KL"))
    )
    (comp (ref "R96")
      (value "RC0603FR-071KL")
      (footprint "0603R")
      (description "RES, 1.00 k, 1%, 0.1 W, 0603")
      (fields
        (field (name "VALUEDISPLAYED") "1.00k")
        (field (name "MANUFACTURER") "Yageo America")
        (field (name "PUBLISHER") "Texas Instruments")
      )
      (libsource (lib "Resistor_0603") (part "RC0603FR-071KL"))
    )
    (comp (ref "R100")
      (value "RC0603FR-0710KL")
      (footprint "0603R")
      (description "RES, 10.0 k, 1%, 0.1 W, 0603")
      (fields
        (field (name "VALUEDISPLAYED") "10.0k")
        (field (name "MANUFACTURER") "Yageo America")
        (field (name "PUBLISHER") "Texas Instruments")
      )
      (libsource (lib "Resistor_0603") (part "RC0603FR-0710KL"))
    )
    (comp (ref "R101")
      (value "RC0603FR-07330RL")
      (footprint "0603R")
      (description "RES, 330, 1%, 0.1 W, 0603")
      (fields
        (field (name "VALUEDISPLAYED") "330")
        (field (name "MANUFACTURER") "Yageo America")
        (field (name "PUBLISHER") "Texas Instruments")
      )
      (libsource (lib "Resistor_0603") (part "RC0603FR-07330RL"))
    )
    (comp (ref "R102")
      (value "CRCW0603499RFKEA")
      (footprint "0603R")
      (description "RES, 499, 1%, 0.1 W, 0603")
      (fields
        (field (name "VALUEDISPLAYED") "499")
        (field (name "MANUFACTURER") "Vishay-Dale")
        (field (name "PUBLISHER") "Texas Instruments")
      )
      (libsource (lib "Miscellaneous Devices") (part "CRCW0603499RFKEA"))
    )
    (comp (ref "R103")
      (value "RC0603FR-0710KL")
      (footprint "0603R")
      (description "RES, 10.0 k, 1%, 0.1 W, 0603")
      (fields
        (field (name "VALUEDISPLAYED") "10.0k")
        (field (name "MANUFACTURER") "Yageo America")
        (field (name "PUBLISHER") "Texas Instruments")
      )
      (libsource (lib "Resistor_0603") (part "RC0603FR-0710KL"))
    )
    (comp (ref "R104")
      (value "CRCW0603499RFKEA")
      (footprint "0603R")
      (description "RES, 499, 1%, 0.1 W, 0603")
      (fields
        (field (name "VALUEDISPLAYED") "499")
        (field (name "MANUFACTURER") "Vishay-Dale")
        (field (name "PUBLISHER") "Texas Instruments")
      )
      (libsource (lib "Miscellaneous Devices") (part "CRCW0603499RFKEA"))
    )
    (comp (ref "R110")
      (value "RC0603FR-0714KL")
      (footprint "0603R")
      (description "RES, 14.0 k, 1%, 0.1 W, 0603")
      (fields
        (field (name "VALUEDISPLAYED") "14.0k")
        (field (name "MANUFACTURER") "Yageo America")
        (field (name "PUBLISHER") "Texas Instruments")
      )
      (libsource (lib "Resistor_0603") (part "RC0603FR-0714KL"))
    )
    (comp (ref "R155")
      (value "RC0603FR-0710RL")
      (footprint "0603R")
      (description "RES, 10.0, 1%, 0.1 W, 0603")
      (fields
        (field (name "VALUEDISPLAYED") "10.0")
        (field (name "MANUFACTURER") "Yageo America")
        (field (name "PUBLISHER") "Texas Instruments")
      )
      (libsource (lib "PMP40182") (part "RC0603FR-0710RL"))
    )
    (comp (ref "R157")
      (value "Resistor")
      (footprint "0603R")
      (description "RES, 100, 1%, 0.1 W, AEC-Q200 Grade 0, 0603")
      (fields
        (field (name "PARTNUMBER") "CRCW0603100RFKEA")
        (field (name "MANUFACTURER") "Vishay-Dale")
        (field (name "VALUEDISPLAYED") "100")
      )
      (libsource (lib "PMP40182") (part "CMP-0021991-4"))
    )
    (comp (ref "R158")
      (value "RC0603JR-070RL")
      (footprint "0603R")
      (description "RES, 0, 5%, 0.1 W, 0603")
      (fields
        (field (name "VALUEDISPLAYED") "0")
        (field (name "MANUFACTURER") "Yageo America")
        (field (name "PUBLISHER") "Texas Instruments")
      )
      (libsource (lib "Resistor_0603") (part "RC0603JR-070RL"))
    )
    (comp (ref "R159")
      (value "Resistor")
      (footprint "0603R")
      (description "RES, 100, 1%, 0.1 W, AEC-Q200 Grade 0, 0603")
      (fields
        (field (name "PARTNUMBER") "CRCW0603100RFKEA")
        (field (name "MANUFACTURER") "Vishay-Dale")
        (field (name "VALUEDISPLAYED") "100")
      )
      (libsource (lib "PMP40182") (part "CMP-0021991-4"))
    )
    (comp (ref "R163")
      (value "Resistor")
      (footprint "0603R")
      (description "RES, 0, 5%, 0.1 W, 0603")
      (fields
        (field (name "PARTNUMBER") "ERJ-3GEY0R00V")
        (field (name "MANUFACTURER") "Panasonic")
        (field (name "VALUEDISPLAYED") "0")
        (field (name "PUBLISHER") "Texas Instruments")
      )
      (libsource (lib "PMP40182") (part "Resistor"))
    )
    (comp (ref "R166")
      (value "RC0603FR-0710KL")
      (footprint "0603R")
      (description "RES, 10.0 k, 1%, 0.1 W, 0603")
      (fields
        (field (name "VALUEDISPLAYED") "10.0k")
        (field (name "MANUFACTURER") "Yageo America")
        (field (name "PUBLISHER") "Texas Instruments")
      )
      (libsource (lib "PMP40182") (part "RC0603FR-0710KL"))
    )
    (comp (ref "R167")
      (value "RC0603FR-0710KL")
      (footprint "0603R")
      (description "RES, 10.0 k, 1%, 0.1 W, 0603")
      (fields
        (field (name "VALUEDISPLAYED") "10.0k")
        (field (name "MANUFACTURER") "Yageo America")
        (field (name "PUBLISHER") "Texas Instruments")
      )
      (libsource (lib "PMP40182") (part "RC0603FR-0710KL"))
    )
    (comp (ref "R173")
      (value "RC0603FR-071KL")
      (footprint "0603R")
      (description "RES, 1.00 k, 1%, 0.1 W, 0603")
      (fields
        (field (name "VALUEDISPLAYED") "1.00k")
        (field (name "MANUFACTURER") "Yageo America")
        (field (name "PUBLISHER") "Texas Instruments")
      )
      (libsource (lib "Resistor_0603") (part "RC0603FR-071KL"))
    )
    (comp (ref "R174")
      (value "RC0603FR-0710RL")
      (footprint "0603R")
      (description "RES, 10.0, 1%, 0.1 W, 0603")
      (fields
        (field (name "VALUEDISPLAYED") "10.0")
        (field (name "MANUFACTURER") "Yageo America")
        (field (name "PUBLISHER") "Texas Instruments")
      )
      (libsource (lib "Resistor_0603") (part "RC0603FR-0710RL"))
    )
    (comp (ref "R175")
      (value "RC0603FR-0710KL")
      (footprint "0603R")
      (description "RES, 10.0 k, 1%, 0.1 W, 0603")
      (fields
        (field (name "VALUEDISPLAYED") "10.0k")
        (field (name "MANUFACTURER") "Yageo America")
        (field (name "PUBLISHER") "Texas Instruments")
      )
      (libsource (lib "Resistor_0603") (part "RC0603FR-0710KL"))
    )
    (comp (ref "R176")
      (value "RC0603FR-071KL")
      (footprint "0603R")
      (description "RES, 1.00 k, 1%, 0.1 W, 0603")
      (fields
        (field (name "VALUEDISPLAYED") "1.00k")
        (field (name "MANUFACTURER") "Yageo America")
        (field (name "PUBLISHER") "Texas Instruments")
      )
      (libsource (lib "Resistor_0603") (part "RC0603FR-071KL"))
    )
    (comp (ref "R177")
      (value "0")
      (footprint "1206")
      (description "RES, 10.0, 1%, 0.25 W, 1206")
      (fields
        (field (name "PARTNUMBER") "ERJ-8ENF10R0V")
        (field (name "MANUFACTURER") "Panasonic")
        (field (name "PUBLISHER") "Texas Instruments")
      )
      (libsource (lib "PWR578A") (part "ERJ-8ENF10R0V"))
    )
    (comp (ref "R178")
      (value "RC0603FR-0710KL")
      (footprint "0603R")
      (description "RES, 10.0 k, 1%, 0.1 W, 0603")
      (fields
        (field (name "VALUEDISPLAYED") "10.0k")
        (field (name "MANUFACTURER") "Yageo America")
        (field (name "PUBLISHER") "Texas Instruments")
      )
      (libsource (lib "PMP40182") (part "RC0603FR-0710KL"))
    )
    (comp (ref "R179")
      (value "RC0603FR-072K2L")
      (footprint "0603R")
      (description "RES, 2.20 k, 1%, 0.1 W, 0603")
      (fields
        (field (name "VALUEDISPLAYED") "2.20k")
        (field (name "MANUFACTURER") "Yageo America")
        (field (name "PUBLISHER") "Texas Instruments")
      )
      (libsource (lib "Resistor_0603") (part "RC0603FR-072K2L"))
    )
    (comp (ref "R180")
      (value "RC0603FR-0710RL")
      (footprint "0603R")
      (description "RES, 10.0, 1%, 0.1 W, 0603")
      (fields
        (field (name "VALUEDISPLAYED") "10.0")
        (field (name "MANUFACTURER") "Yageo America")
        (field (name "PUBLISHER") "Texas Instruments")
      )
      (libsource (lib "Resistor_0603") (part "RC0603FR-0710RL"))
    )
    (comp (ref "R181")
      (value "RC0603FR-072K2L")
      (footprint "0603R")
      (description "RES, 2.20 k, 1%, 0.1 W, 0603")
      (fields
        (field (name "VALUEDISPLAYED") "2.20k")
        (field (name "MANUFACTURER") "Yageo America")
        (field (name "PUBLISHER") "Texas Instruments")
      )
      (libsource (lib "Resistor_0603") (part "RC0603FR-072K2L"))
    )
    (comp (ref "R182")
      (value "RC0603FR-0710RL")
      (footprint "0603R")
      (description "RES, 10.0, 1%, 0.1 W, 0603")
      (fields
        (field (name "VALUEDISPLAYED") "10.0")
        (field (name "MANUFACTURER") "Yageo America")
        (field (name "PUBLISHER") "Texas Instruments")
      )
      (libsource (lib "Resistor_0603") (part "RC0603FR-0710RL"))
    )
    (comp (ref "R183")
      (value "RC0603FR-0775KL")
      (footprint "0603R")
      (description "RES, 75.0 k, 1%, 0.1 W, 0603")
      (fields
        (field (name "VALUEDISPLAYED") "75.0k")
        (field (name "MANUFACTURER") "Yageo America")
        (field (name "PUBLISHER") "Texas Instruments")
      )
      (libsource (lib "Resistor_0603") (part "RC0603FR-0775KL"))
    )
    (comp (ref "R184")
      (value "RC0603FR-071KL")
      (footprint "0603R")
      (description "RES, 1.00 k, 1%, 0.1 W, 0603")
      (fields
        (field (name "VALUEDISPLAYED") "1.00k")
        (field (name "MANUFACTURER") "Yageo America")
        (field (name "PUBLISHER") "Texas Instruments")
      )
      (libsource (lib "Resistor_0603") (part "RC0603FR-071KL"))
    )
    (comp (ref "R185")
      (value "RC0603FR-0710KL")
      (footprint "0603R")
      (description "RES, 10.0 k, 1%, 0.1 W, 0603")
      (fields
        (field (name "VALUEDISPLAYED") "10.0k")
        (field (name "MANUFACTURER") "Yageo America")
        (field (name "PUBLISHER") "Texas Instruments")
      )
      (libsource (lib "PMP40182") (part "RC0603FR-0710KL"))
    )
    (comp (ref "U6")
      (value "INA828ID")
      (footprint "D0008A_N")
      (description "50-uV Offset, 7-nV/√Hz Noise, Low-Power, Precision Instrumentation Amplifier, D0008A (SOIC-8)")
      (fields
        (field (name "ALTERNATE PARTNUMBER") "INA828IDR")
        (field (name "MANUFACTURER") "Texas Instruments")
        (field (name "PARTNUMBER") "INA828ID")
      )
      (libsource (lib "SV601272A") (part "CMP-0079943-1"))
    )
    (comp (ref "U8")
      (value "TL331IDBVR")
      (footprint "DBV0005A_N")
      (description "SINGLE DIFFERENTIAL COMPARATOR, DBV0005A (SOT-5)")
      (fields
        (field (name "MANUFACTURER") "Texas Instruments")
        (field (name "ALTERNATE PARTNUMBER") "TL331IDBVT")
        (field (name "SYMBOLCREATOR") "a0411947")
        (field (name "PUBLISHER") "Texas Instruments")
      )
      (libsource (lib "TI_Pre_Release") (part "TL331IDBVR"))
    )
    (comp (ref "U9")
      (value "OPA180IDR")
      (footprint "D0008A_N")
      (fields
        (field (name "ALTERNATE PARTNUMBER") "OPA180ID")
        (field (name "MANUFACTURER") "Texas Instruments")
        (field (name "SYMBOLCREATOR") "a0411595/a0412235")
        (field (name "PUBLISHER") "Texas Instruments")
      )
      (libsource (lib "TI_Pre_Release") (part "OPA180IDR"))
    )
    (comp (ref "U15")
      (value "OPA2180IDGKR")
      (footprint "DGK0008A_N")
      (fields (field (name "MANUFACTURER") "Texas Instruments"))
      (libsource (lib "Altium Content Vault") (part "TI-OPA-8_2"))
    )
    (comp (ref "U19")
      (value "1655")
      (footprint "ADA-RGB-1655_V")
      (fields (field (name "MANUFACTURER") "Adafruit-Industries-LLC"))
      (libsource (lib "Altium Content Vault") (part "ADA-RGB-1655-4"))
    )
    (comp (ref "U30")
      (value "LM5106MM/NOPB")
      (footprint "DGS0010A_N")
      (description "100V Half-Bridge Gate Driver with Programmable Dead-Time, 10-pin MSOP, Pb-Free")
      (fields (field (name "MANUFACTURER") "Texas Instruments"))
      (libsource (lib "Altium Content Vault") (part "IN-MOSDRV-LM5106-10"))
    )
    (comp (ref "U31")
      (value "TL594CPWR")
      (footprint "PW0016A_M")
      (fields (field (name "MANUFACTURER") "Texas Instruments"))
      (libsource (lib "Altium Content Vault") (part "TI-594PW16"))
    )
    (comp (ref "U32")
      (value "LM5060Q1MM/NOPB")
      (footprint "DGS0010A_N")
      (description "High-Side Protection Controller with Low Quiescent Current, 10-pin MSOP, Pb-Free")
      (fields (field (name "MANUFACTURER") "Texas Instruments"))
      (libsource (lib "Altium Content Vault") (part "PM-CNTL-LM5060MM-10"))
    )
    (comp (ref "U33")
      (value "OPA2180IDGKR")
      (footprint "DGK0008A_N")
      (fields (field (name "MANUFACTURER") "Texas Instruments"))
      (libsource (lib "Altium Content Vault") (part "TI-OPA-8_2"))
    )
    (comp (ref "U37")
      (value "TPD4E002DRLR")
      (footprint "DRL0005A_L")
      (fields (field (name "MANUFACTURER") "Texas Instruments"))
      (libsource (lib "Altium Content Vault") (part "TI-TPD4E002-SOT_DRL-5"))
    )
  )
  (nets
    (net (code "3") (name "+3.3v") (class "Default")
      (node (ref "C30") (pin "2") (pinfunction "2_2") (pintype "passive"))
      (node (ref "U19") (pin "1") (pinfunction "VDD_1") (pintype "power_in"))
    )
    (net (code "4") (name "+5VA") (class "Default")
      (node (ref "R38") (pin "2") (pinfunction "2_2") (pintype "passive"))
      (node (ref "R87") (pin "2") (pinfunction "2_2") (pintype "passive"))
    )
    (net (code "5") (name "+9VA") (class "Default")
      (node (ref "R155") (pin "1") (pinfunction "1_1") (pintype "passive"))
      (node (ref "R174") (pin "1") (pinfunction "1_1") (pintype "passive"))
      (node (ref "R181") (pin "1") (pinfunction "1_1") (pintype "passive"))
      (node (ref "R182") (pin "2") (pinfunction "2_2") (pintype "passive"))
      (node (ref "R183") (pin "2") (pinfunction "2_2") (pintype "passive"))
      (node (ref "R67") (pin "2") (pinfunction "2_2") (pintype "passive"))
      (node (ref "R74") (pin "1") (pinfunction "1_1") (pintype "passive"))
      (node (ref "U6") (pin "7") (pinfunction "V+_7") (pintype "power_in"))
      (node (ref "U8") (pin "5") (pinfunction "V+_5") (pintype "power_in"))
    )
    (net (code "6") (name "-5V") (class "Default")
      (node (ref "C122") (pin "2") (pinfunction "2_2") (pintype "passive"))
      (node (ref "C47") (pin "1") (pinfunction "1_1") (pintype "passive"))
      (node (ref "U6") (pin "4") (pinfunction "V-_4") (pintype "power_in"))
    )
    (net (code "7") (name "-5VA") (class "Default")
      (node (ref "U8") (pin "2") (pinfunction "V-/GND_2") (pintype "power_in"))
    )
    (net (code "8") (name "/BAT_N") (class "Default")
      (node (ref "BN1") (pin "2") (pinfunction "2_2") (pintype "passive"))
      (node (ref "C48") (pin "2") (pinfunction "2_2") (pintype "passive"))
      (node (ref "R159") (pin "2") (pinfunction "2_2") (pintype "passive"))
      (node (ref "R177") (pin "2") (pinfunction "2_2") (pintype "passive"))
      (node (ref "U37") (pin "1") (pinfunction "IO1_1") (pintype "passive"))
    )
    (net (code "9") (name "/BAT_P") (class "Default")
      (node (ref "BP1") (pin "1") (pinfunction "1_1") (pintype "passive"))
      (node (ref "C48") (pin "1") (pinfunction "1_1") (pintype "passive"))
      (node (ref "F1") (pin "2") (pintype "passive"))
      (node (ref "R157") (pin "2") (pinfunction "2_2") (pintype "passive"))
      (node (ref "U37") (pin "4") (pinfunction "IO3_4") (pintype "passive"))
    )
    (net (code "10") (name "/CC") (class "Default")
      (node (ref "C93") (pin "1") (pinfunction "1_1") (pintype "passive"))
      (node (ref "D17") (pin "1") (pinfunction "K_1") (pintype "passive"))
      (node (ref "R101") (pin "2") (pinfunction "2_2") (pintype "passive"))
      (node (ref "U9") (pin "6") (pinfunction "OUT_6") (pintype "output"))
    )
    (net (code "11") (name "/CHARGE.Enable") (class "Default")
      (node (ref "R44") (pin "1") (pinfunction "1_1") (pintype "passive"))
      (node (ref "R7") (pin "1") (pinfunction "1_1") (pintype "passive"))
    )
    (net (code "12") (name "/CHG.EN") (class "Default")
      (node (ref "D10") (pin "2") (pinfunction "A_2") (pintype "passive"))
      (node (ref "Q10") (pin "3") (pinfunction "D_3") (pintype "passive"))
      (node (ref "R44") (pin "2") (pinfunction "2_2") (pintype "passive"))
      (node (ref "U30") (pin "7") (pinfunction "EN_7") (pintype "input"))
    )
    (net (code "13") (name "/CS_N") (class "Default")
      (node (ref "R31") (pin "3") (pinfunction "3_3") (pintype "passive"))
      (node (ref "R60") (pin "1") (pinfunction "1_1") (pintype "passive"))
    )
    (net (code "14") (name "/CS_P") (class "Default")
      (node (ref "R31") (pin "4") (pinfunction "4_4") (pintype "passive"))
      (node (ref "R61") (pin "1") (pinfunction "1_1") (pintype "passive"))
    )
    (net (code "15") (name "/CV") (class "Default")
      (node (ref "C170") (pin "1") (pinfunction "1_1") (pintype "passive"))
      (node (ref "D18") (pin "1") (pinfunction "K_1") (pintype "passive"))
      (node (ref "R184") (pin "2") (pinfunction "2_2") (pintype "passive"))
      (node (ref "U33") (pin "7") (pinfunction "OUT_B_7") (pintype "output"))
    )
    (net (code "16") (name "/FAULT") (class "Default")
      (node (ref "C177") (pin "2") (pinfunction "2_2") (pintype "passive"))
      (node (ref "Q10") (pin "1") (pinfunction "G_1") (pintype "passive"))
      (node (ref "R158") (pin "1") (pinfunction "1_1") (pintype "passive"))
      (node (ref "R7") (pin "2") (pinfunction "2_2") (pintype "passive"))
      (node (ref "R8") (pin "2") (pinfunction "2_2") (pintype "passive"))
    )
    (net (code "17") (name "/IOUT_Sense") (class "Default")
      (node (ref "R86") (pin "1") (pinfunction "1_1") (pintype "passive"))
      (node (ref "R88") (pin "1") (pinfunction "1_1") (pintype "passive"))
      (node (ref "U6") (pin "6") (pinfunction "OUT_6") (pintype "output"))
    )
    (net (code "19") (name "/ISet") (class "Default")
      (node (ref "R77") (pin "1") (pinfunction "1_1") (pintype "passive"))
    )
    (net (code "20") (name "/Ivcom") (class "Default")
      (node (ref "U6") (pin "5") (pinfunction "REF_5") (pintype "input"))
    )
    (net (code "21") (name "/LED.SDI") (class "Default")
      (node (ref "U19") (pin "4") (pinfunction "DIN_4") (pintype "input"))
    )
    (net (code "22") (name "/LED.SDO") (class "Default")
      (node (ref "U19") (pin "2") (pinfunction "DOUT_2") (pintype "output"))
    )
    (net (code "23") (name "/OUTPUT.Enable") (class "Default")
      (node (ref "U32") (pin "5") (pinfunction "EN_5") (pintype "input"))
    )
    (net (code "24") (name "/OUT_GATE") (class "Default")
      (node (ref "D12") (pin "2") (pinfunction "A_2") (pintype "passive"))
      (node (ref "D4") (pin "1") (pinfunction "K_1") (pintype "passive"))
      (node (ref "D5") (pin "1") (pinfunction "K_1") (pintype "passive"))
      (node (ref "Q4") (pin "4") (pinfunction "G_4") (pintype "passive"))
      (node (ref "Q5") (pin "4") (pinfunction "G_4") (pintype "passive"))
      (node (ref "Q8") (pin "3") (pinfunction "C_3") (pintype "passive"))
      (node (ref "R36") (pin "2") (pinfunction "2_2") (pintype "passive"))
    )
    (net (code "25") (name "/OUT_OVP") (class "Default")
      (node (ref "C168") (pin "2") (pinfunction "2_2") (pintype "passive"))
      (node (ref "D4") (pin "2") (pinfunction "A_2") (pintype "passive"))
      (node (ref "Q4") (pin "5") (pinfunction "D_5") (pintype "passive"))
      (node (ref "Q4") (pin "6") (pinfunction "D_6") (pintype "passive"))
      (node (ref "Q4") (pin "7") (pinfunction "D_7") (pintype "passive"))
      (node (ref "Q4") (pin "8") (pinfunction "D_8") (pintype "passive"))
      (node (ref "R110") (pin "1") (pinfunction "1_1") (pintype "passive"))
      (node (ref "R110") (pin "2") (pinfunction "2_2") (pintype "passive"))
      (node (ref "R31") (pin "1") (pinfunction "1_1") (pintype "passive"))
      (node (ref "R65") (pin "1") (pinfunction "1_1") (pintype "passive"))
      (node (ref "U32") (pin "3") (pinfunction "OVP_3") (pintype "input"))
    )
    (net (code "26") (name "/OVP_BOOST_OC") (class "Default")
      (node (ref "D10") (pin "1") (pinfunction "K_1") (pintype "passive"))
    )
    (net (code "27") (name "/PWM") (class "Default")
      (node (ref "R180") (pin "1") (pinfunction "1_1") (pintype "passive"))
      (node (ref "R183") (pin "1") (pinfunction "1_1") (pintype "passive"))
      (node (ref "U31") (pin "11") (pinfunction "C2_11") (pintype "passive"))
    )
    (net (code "28") (name "/PWM_HO") (class "Default")
      (node (ref "D2") (pin "1") (pinfunction "K_1") (pintype "passive"))
      (node (ref "R32") (pin "2") (pinfunction "2_2") (pintype "passive"))
      (node (ref "U30") (pin "3") (pinfunction "HO_3") (pintype "output"))
    )
    (net (code "29") (name "/PWM_HS") (class "Default")
      (node (ref "C167") (pin "2") (pinfunction "2_2") (pintype "passive"))
      (node (ref "D1") (pin "2") (pinfunction "A_2") (pintype "passive"))
      (node (ref "D7") (pin "1") (pinfunction "K_1") (pintype "passive"))
      (node (ref "L4") (pin "1") (pinfunction "1_1") (pintype "passive"))
      (node (ref "Q6") (pin "1") (pinfunction "S_1") (pintype "passive"))
      (node (ref "Q6") (pin "2") (pinfunction "S_2") (pintype "passive"))
      (node (ref "Q6") (pin "3") (pinfunction "S_3") (pintype "passive"))
      (node (ref "Q9") (pin "5") (pinfunction "D_5") (pintype "passive"))
      (node (ref "Q9") (pin "6") (pinfunction "D_6") (pintype "passive"))
      (node (ref "Q9") (pin "7") (pinfunction "D_7") (pintype "passive"))
      (node (ref "Q9") (pin "8") (pinfunction "D_8") (pintype "passive"))
      (node (ref "R29") (pin "1") (pinfunction "1_1") (pintype "passive"))
      (node (ref "U30") (pin "4") (pinfunction "HS_4") (pintype "input"))
    )
    (net (code "30") (name "/PWM_LO") (class "Default")
      (node (ref "D9") (pin "1") (pinfunction "K_1") (pintype "passive"))
      (node (ref "R33") (pin "2") (pinfunction "2_2") (pintype "passive"))
      (node (ref "U30") (pin "10") (pinfunction "LO_10") (pintype "output"))
    )
    (net (code "31") (name "/Reverse_EN") (class "Default")
      (node (ref "D16") (pin "1") (pinfunction "K_1") (pintype "passive"))
      (node (ref "R66") (pin "1") (pinfunction "1_1") (pintype "passive"))
      (node (ref "R74") (pin "2") (pinfunction "2_2") (pintype "passive"))
      (node (ref "U32") (pin "4") (pinfunction "UVLO_4") (pintype "input"))
      (node (ref "U8") (pin "4") (pinfunction "OUT_4") (pintype "output"))
    )
    (net (code "32") (name "/VFB_594") (class "Default")
      (node (ref "D17") (pin "2") (pinfunction "A_2") (pintype "passive"))
      (node (ref "D18") (pin "2") (pinfunction "A_2") (pintype "passive"))
      (node (ref "R28") (pin "1") (pinfunction "1_1") (pintype "passive"))
      (node (ref "R92") (pin "2") (pinfunction "2_2") (pintype "passive"))
    )
    (net (code "33") (name "/VOUT_Sense") (class "Default")
      (node (ref "C183") (pin "1") (pinfunction "1_1") (pintype "passive"))
      (node (ref "R185") (pin "2") (pinfunction "2_2") (pintype "passive"))
      (node (ref "R94") (pin "1") (pinfunction "1_1") (pintype "passive"))
      (node (ref "R96") (pin "1") (pinfunction "1_1") (pintype "passive"))
      (node (ref "U33") (pin "1") (pinfunction "OUT_A_1") (pintype "output"))
    )
    (net (code "34") (name "/VS_N") (class "Default")
      (node (ref "BN1") (pin "1") (pinfunction "1_1") (pintype "passive"))
      (node (ref "R163") (pin "2") (pinfunction "2_2") (pintype "passive"))
      (node (ref "U37") (pin "3") (pinfunction "IO2_3") (pintype "passive"))
    )
    (net (code "35") (name "/VS_P") (class "Default")
      (node (ref "BP1") (pin "2") (pinfunction "2_2") (pintype "passive"))
      (node (ref "R37") (pin "2") (pinfunction "2_2") (pintype "passive"))
      (node (ref "U37") (pin "5") (pinfunction "IO4_5") (pintype "passive"))
      (node (ref "U8") (pin "3") (pinfunction "IN+_3") (pintype "input"))
    )
    (net (code "36") (name "/VSense") (class "Default")
      (node (ref "C100") (pin "1") (pinfunction "1_1") (pintype "passive"))
      (node (ref "R173") (pin "2") (pinfunction "2_2") (pintype "passive"))
    )
    (net (code "37") (name "/VSet") (class "Default")
      (node (ref "R93") (pin "1") (pinfunction "1_1") (pintype "passive"))
    )
    (net (code "38") (name "/V_HV") (class "Default")
      (node (ref "R35") (pin "1") (pinfunction "1_1") (pintype "passive"))
    )
    (net (code "41") (name "12VA") (class "Default")
      (node (ref "C119") (pin "1") (pinfunction "1_1") (pintype "passive"))
      (node (ref "C120") (pin "2") (pinfunction "2_2") (pintype "passive"))
      (node (ref "C121") (pin "2") (pinfunction "2_2") (pintype "passive"))
      (node (ref "C43") (pin "1") (pinfunction "1_1") (pintype "passive"))
    )
    (net (code "42") (name "AGND") (class "Default")
      (node (ref "C100") (pin "2") (pinfunction "2_2") (pintype "passive"))
      (node (ref "C119") (pin "2") (pinfunction "2_2") (pintype "passive"))
      (node (ref "C120") (pin "1") (pinfunction "1_1") (pintype "passive"))
      (node (ref "C121") (pin "1") (pinfunction "1_1") (pintype "passive"))
      (node (ref "C122") (pin "1") (pinfunction "1_1") (pintype "passive"))
      (node (ref "C43") (pin "2") (pinfunction "2_2") (pintype "passive"))
      (node (ref "C45") (pin "2") (pinfunction "2_2") (pintype "passive"))
      (node (ref "C46") (pin "2") (pinfunction "2_2") (pintype "passive"))
      (node (ref "C47") (pin "2") (pinfunction "2_2") (pintype "passive"))
      (node (ref "C55") (pin "1") (pinfunction "1_1") (pintype "passive"))
      (node (ref "C56") (pin "2") (pinfunction "2_2") (pintype "passive"))
      (node (ref "C79") (pin "2") (pinfunction "2_2") (pintype "passive"))
      (node (ref "C82") (pin "2") (pinfunction "2_2") (pintype "passive"))
      (node (ref "C85") (pin "1") (pinfunction "1_1") (pintype "passive"))
      (node (ref "C86") (pin "2") (pinfunction "2_2") (pintype "passive"))
      (node (ref "C88") (pin "1") (pinfunction "1_1") (pintype "passive"))
      (node (ref "C89") (pin "1") (pinfunction "1_1") (pintype "passive"))
      (node (ref "C90") (pin "1") (pinfunction "1_1") (pintype "passive"))
      (node (ref "C91") (pin "2") (pinfunction "2_2") (pintype "passive"))
      (node (ref "C95") (pin "1") (pinfunction "1_1") (pintype "passive"))
      (node (ref "C96") (pin "1") (pinfunction "1_1") (pintype "passive"))
      (node (ref "C99") (pin "2") (pinfunction "2_2") (pintype "passive"))
      (node (ref "R100") (pin "1") (pinfunction "1_1") (pintype "passive"))
      (node (ref "R166") (pin "2") (pinfunction "2_2") (pintype "passive"))
      (node (ref "R175") (pin "2") (pinfunction "2_2") (pintype "passive"))
      (node (ref "R176") (pin "2") (pinfunction "2_2") (pintype "passive"))
      (node (ref "R89") (pin "1") (pinfunction "1_1") (pintype "passive"))
      (node (ref "U15") (pin "4") (pinfunction "V-_4") (pintype "power_in"))
      (node (ref "U31") (pin "10") (pinfunction "E2_10") (pintype "passive"))
      (node (ref "U31") (pin "9") (pinfunction "E1_9") (pintype "passive"))
      (node (ref "U33") (pin "4") (pinfunction "V-_4") (pintype "power_in"))
      (node (ref "U37") (pin "2") (pinfunction "GND_2") (pintype "power_in"))
      (node (ref "U9") (pin "4") (pinfunction "V-_4") (pintype "power_in"))
    )
    (net (code "43") (name "GND") (class "Default")
      (node (ref "C30") (pin "1") (pinfunction "1_1") (pintype "passive"))
    )
    (net (code "44") (name "Net-(C10-+)") (class "Default")
      (node (ref "C10") (pin "1") (pinfunction "+_1") (pintype "passive"))
      (node (ref "C11") (pin "1") (pinfunction "1_1") (pintype "passive"))
      (node (ref "C12") (pin "1") (pinfunction "1_1") (pintype "passive"))
      (node (ref "D1") (pin "1") (pinfunction "K_1") (pintype "passive"))
      (node (ref "Q6") (pin "5") (pinfunction "D_5") (pintype "passive"))
      (node (ref "Q6") (pin "6") (pinfunction "D_6") (pintype "passive"))
      (node (ref "Q6") (pin "7") (pinfunction "D_7") (pintype "passive"))
      (node (ref "Q6") (pin "8") (pinfunction "D_8") (pintype "passive"))
      (node (ref "R35") (pin "2") (pinfunction "2_2") (pintype "passive"))
    )
    (net (code "45") (name "Net-(C24-+)") (class "Default")
      (node (ref "C17") (pin "1") (pinfunction "1_1") (pintype "passive"))
      (node (ref "C20") (pin "1") (pinfunction "1_1") (pintype "passive"))
      (node (ref "C24") (pin "1") (pinfunction "+_1") (pintype "passive"))
      (node (ref "L4") (pin "2") (pinfunction "2_2") (pintype "passive"))
      (node (ref "R31") (pin "2") (pinfunction "2_2") (pintype "passive"))
    )
    (net (code "46") (name "Net-(C79-Pad1)") (class "Default")
      (node (ref "C79") (pin "1") (pinfunction "1_1") (pintype "passive"))
      (node (ref "C80") (pin "1") (pinfunction "1_1") (pintype "passive"))
      (node (ref "R102") (pin "1") (pinfunction "1_1") (pintype "passive"))
      (node (ref "R60") (pin "2") (pinfunction "2_2") (pintype "passive"))
    )
    (net (code "47") (name "Net-(C80-Pad2)") (class "Default")
      (node (ref "C80") (pin "2") (pinfunction "2_2") (pintype "passive"))
      (node (ref "C82") (pin "1") (pinfunction "1_1") (pintype "passive"))
      (node (ref "R104") (pin "1") (pinfunction "1_1") (pintype "passive"))
      (node (ref "R61") (pin "2") (pinfunction "2_2") (pintype "passive"))
    )
    (net (code "48") (name "Net-(C91-Pad1)") (class "Default")
      (node (ref "C91") (pin "1") (pinfunction "1_1") (pintype "passive"))
      (node (ref "R95") (pin "2") (pinfunction "2_2") (pintype "passive"))
    )
    (net (code "49") (name "Net-(C92-Pad1)") (class "Default")
      (node (ref "C92") (pin "1") (pinfunction "1_1") (pintype "passive"))
      (node (ref "R101") (pin "1") (pinfunction "1_1") (pintype "passive"))
    )
    (net (code "50") (name "Net-(C118-Pad1)") (class "Default")
      (node (ref "C118") (pin "1") (pinfunction "1_1") (pintype "passive"))
      (node (ref "R184") (pin "1") (pinfunction "1_1") (pintype "passive"))
    )
    (net (code "51") (name "Net-(C166-Pad2)") (class "Default")
      (node (ref "C166") (pin "2") (pinfunction "2_2") (pintype "passive"))
      (node (ref "R29") (pin "2") (pinfunction "2_2") (pintype "passive"))
    )
    (net (code "52") (name "Net-(D2-A)") (class "Default")
      (node (ref "D2") (pin "2") (pinfunction "A_2") (pintype "passive"))
      (node (ref "Q6") (pin "4") (pinfunction "G_4") (pintype "passive"))
      (node (ref "R32") (pin "1") (pinfunction "1_1") (pintype "passive"))
    )
    (net (code "53") (name "Net-(D5-A)") (class "Default")
      (node (ref "D5") (pin "2") (pinfunction "A_2") (pintype "passive"))
      (node (ref "F1") (pin "1") (pintype "passive"))
      (node (ref "Q5") (pin "5") (pinfunction "D_5") (pintype "passive"))
      (node (ref "Q5") (pin "6") (pinfunction "D_6") (pintype "passive"))
      (node (ref "Q5") (pin "7") (pinfunction "D_7") (pintype "passive"))
      (node (ref "Q5") (pin "8") (pinfunction "D_8") (pintype "passive"))
    )
    (net (code "54") (name "Net-(D8-A)") (class "Default")
      (node (ref "D8") (pin "2") (pinfunction "A_2") (pintype "passive"))
      (node (ref "Q4") (pin "1") (pinfunction "S_1") (pintype "passive"))
      (node (ref "Q4") (pin "2") (pinfunction "S_2") (pintype "passive"))
      (node (ref "Q4") (pin "3") (pinfunction "S_3") (pintype "passive"))
      (node (ref "Q5") (pin "1") (pinfunction "S_1") (pintype "passive"))
      (node (ref "Q5") (pin "2") (pinfunction "S_2") (pintype "passive"))
      (node (ref "Q5") (pin "3") (pinfunction "S_3") (pintype "passive"))
      (node (ref "Q8") (pin "2") (pinfunction "E_2") (pintype "passive"))
    )
    (net (code "55") (name "Net-(D8-K)") (class "Default")
      (node (ref "C74") (pin "1") (pinfunction "1_1") (pintype "passive"))
      (node (ref "D8") (pin "1") (pinfunction "K_1") (pintype "passive"))
      (node (ref "Q8") (pin "1") (pinfunction "B_1") (pintype "passive"))
      (node (ref "R34") (pin "1") (pinfunction "1_1") (pintype "passive"))
    )
    (net (code "56") (name "Net-(D9-A)") (class "Default")
      (node (ref "D9") (pin "2") (pinfunction "A_2") (pintype "passive"))
      (node (ref "Q9") (pin "4") (pinfunction "G_4") (pintype "passive"))
      (node (ref "R33") (pin "1") (pinfunction "1_1") (pintype "passive"))
    )
    (net (code "57") (name "Net-(D11-A)") (class "Default")
      (node (ref "C171") (pin "1") (pinfunction "1_1") (pintype "passive"))
      (node (ref "D11") (pin "2") (pinfunction "A_2") (pintype "passive"))
      (node (ref "R182") (pin "1") (pinfunction "1_1") (pintype "passive"))
      (node (ref "U30") (pin "1") (pinfunction "VDD_1") (pintype "power_in"))
    )
    (net (code "58") (name "Net-(D11-K)") (class "Default")
      (node (ref "C167") (pin "1") (pinfunction "1_1") (pintype "passive"))
      (node (ref "D11") (pin "1") (pinfunction "K_1") (pintype "passive"))
      (node (ref "U30") (pin "2") (pinfunction "HB_2") (pintype "input"))
    )
    (net (code "59") (name "Net-(D12-K)") (class "Default")
      (node (ref "D12") (pin "1") (pinfunction "K_1") (pintype "passive"))
      (node (ref "R36") (pin "1") (pinfunction "1_1") (pintype "passive"))
      (node (ref "U32") (pin "10") (pinfunction "GATE_10") (pintype "output"))
    )
    (net (code "60") (name "Net-(D15-K)") (class "Default")
      (node (ref "C97") (pin "1") (pinfunction "1_1") (pintype "passive"))
      (node (ref "D15") (pin "1") (pinfunction "K_1") (pintype "passive"))
      (node (ref "R181") (pin "2") (pinfunction "2_2") (pintype "passive"))
      (node (ref "R39") (pin "2") (pinfunction "2_2") (pintype "passive"))
      (node (ref "R42") (pin "1") (pinfunction "1_1") (pintype "passive"))
      (node (ref "U32") (pin "2") (pinfunction "VIN_2") (pintype "power_in"))
    )
    (net (code "61") (name "Net-(D16-A)") (class "Default")
      (node (ref "D16") (pin "2") (pinfunction "A_2") (pintype "passive"))
      (node (ref "R75") (pin "2") (pinfunction "2_2") (pintype "passive"))
    )
    (net (code "62") (name "Net-(R24-Pad1)") (class "Default")
      (node (ref "R24") (pin "1") (pinfunction "1_1") (pintype "passive"))
      (node (ref "U6") (pin "1") (pinfunction "RG_1") (pintype "passive"))
    )
    (net (code "63") (name "Net-(R24-Pad2)") (class "Default")
      (node (ref "R24") (pin "2") (pinfunction "2_2") (pintype "passive"))
      (node (ref "U6") (pin "8") (pinfunction "RG_8") (pintype "passive"))
    )
    (net (code "64") (name "Net-(R90-Pad2)") (class "Default")
      (node (ref "R90") (pin "2") (pinfunction "2_2") (pintype "passive"))
      (node (ref "R95") (pin "1") (pinfunction "1_1") (pintype "passive"))
    )
    (net (code "65") (name "Net-(R157-Pad1)") (class "Default")
      (node (ref "R157") (pin "1") (pinfunction "1_1") (pintype "passive"))
      (node (ref "R167") (pin "1") (pinfunction "1_1") (pintype "passive"))
      (node (ref "R37") (pin "1") (pinfunction "1_1") (pintype "passive"))
    )
    (net (code "66") (name "Net-(R159-Pad1)") (class "Default")
      (node (ref "R159") (pin "1") (pinfunction "1_1") (pintype "passive"))
      (node (ref "R163") (pin "1") (pinfunction "1_1") (pintype "passive"))
      (node (ref "R178") (pin "1") (pinfunction "1_1") (pintype "passive"))
    )
    (net (code "67") (name "Net-(U6-IN+)") (class "Default")
      (node (ref "C46") (pin "1") (pinfunction "1_1") (pintype "passive"))
      (node (ref "C81") (pin "2") (pinfunction "2_2") (pintype "passive"))
      (node (ref "R104") (pin "2") (pinfunction "2_2") (pintype "passive"))
      (node (ref "U6") (pin "3") (pinfunction "IN+_3") (pintype "input"))
    )
    (net (code "68") (name "Net-(U6-IN-)") (class "Default")
      (node (ref "C45") (pin "1") (pinfunction "1_1") (pintype "passive"))
      (node (ref "C81") (pin "1") (pinfunction "1_1") (pintype "passive"))
      (node (ref "R102") (pin "2") (pinfunction "2_2") (pintype "passive"))
      (node (ref "U6") (pin "2") (pinfunction "IN-_2") (pintype "input"))
    )
    (net (code "69") (name "Net-(U8-IN-)") (class "Default")
      (node (ref "C87") (pin "2") (pinfunction "2_2") (pintype "passive"))
      (node (ref "R43") (pin "2") (pinfunction "2_2") (pintype "passive"))
      (node (ref "R67") (pin "1") (pinfunction "1_1") (pintype "passive"))
      (node (ref "U8") (pin "1") (pinfunction "IN-_1") (pintype "input"))
    )
    (net (code "70") (name "Net-(U9A-IN+)") (class "Default")
      (node (ref "C55") (pin "2") (pinfunction "2_2") (pintype "passive"))
      (node (ref "R77") (pin "2") (pinfunction "2_2") (pintype "passive"))
      (node (ref "U9") (pin "3") (pinfunction "IN+_3") (pintype "input"))
    )
    (net (code "71") (name "Net-(U9A-IN-)") (class "Default")
      (node (ref "C92") (pin "2") (pinfunction "2_2") (pintype "passive"))
      (node (ref "C93") (pin "2") (pinfunction "2_2") (pintype "passive"))
      (node (ref "R88") (pin "2") (pinfunction "2_2") (pintype "passive"))
      (node (ref "U9") (pin "2") (pinfunction "IN-_2") (pintype "input"))
    )
    (net (code "72") (name "Net-(U9A-V+)") (class "Default")
      (node (ref "C56") (pin "1") (pinfunction "1_1") (pintype "passive"))
      (node (ref "C88") (pin "2") (pinfunction "2_2") (pintype "passive"))
      (node (ref "R38") (pin "1") (pinfunction "1_1") (pintype "passive"))
      (node (ref "U9") (pin "7") (pinfunction "V+_7") (pintype "power_in"))
    )
    (net (code "73") (name "Net-(U15A-IN_A+)") (class "Default")
      (node (ref "C89") (pin "2") (pinfunction "2_2") (pintype "passive"))
      (node (ref "R86") (pin "2") (pinfunction "2_2") (pintype "passive"))
      (node (ref "U15") (pin "3") (pinfunction "IN_A+_3") (pintype "input"))
    )
    (net (code "74") (name "Net-(U15A-IN_A-)") (class "Default")
      (node (ref "R89") (pin "2") (pinfunction "2_2") (pintype "passive"))
      (node (ref "R90") (pin "1") (pinfunction "1_1") (pintype "passive"))
      (node (ref "U15") (pin "2") (pinfunction "IN_A-_2") (pintype "input"))
    )
    (net (code "75") (name "Net-(U15A-OUT_A)") (class "Default")
      (node (ref "C85") (pin "2") (pinfunction "2_2") (pintype "passive"))
      (node (ref "C86") (pin "1") (pinfunction "1_1") (pintype "passive"))
      (node (ref "R87") (pin "1") (pinfunction "1_1") (pintype "passive"))
      (node (ref "U15") (pin "1") (pinfunction "OUT_A_1") (pintype "output"))
      (node (ref "U15") (pin "8") (pinfunction "V+_8") (pintype "power_in"))
    )
    (net (code "76") (name "Net-(U15B-IN_B+)") (class "Default")
      (node (ref "C96") (pin "2") (pinfunction "2_2") (pintype "passive"))
      (node (ref "R175") (pin "1") (pinfunction "1_1") (pintype "passive"))
      (node (ref "R94") (pin "2") (pinfunction "2_2") (pintype "passive"))
      (node (ref "U15") (pin "5") (pinfunction "IN_B+_5") (pintype "input"))
    )
    (net (code "77") (name "Net-(U15B-IN_B-)") (class "Default")
      (node (ref "R100") (pin "2") (pinfunction "2_2") (pintype "passive"))
      (node (ref "R103") (pin "1") (pinfunction "1_1") (pintype "passive"))
      (node (ref "U15") (pin "6") (pinfunction "IN_B-_6") (pintype "input"))
    )
    (net (code "78") (name "Net-(U15B-OUT_B)") (class "Default")
      (node (ref "R103") (pin "2") (pinfunction "2_2") (pintype "passive"))
      (node (ref "R173") (pin "1") (pinfunction "1_1") (pintype "passive"))
      (node (ref "U15") (pin "7") (pinfunction "OUT_B_7") (pintype "output"))
    )
    (net (code "79") (name "Net-(U30-IN)") (class "Default")
      (node (ref "R180") (pin "2") (pinfunction "2_2") (pintype "passive"))
      (node (ref "U30") (pin "8") (pinfunction "IN_8") (pintype "input"))
    )
    (net (code "80") (name "Net-(U30-RDT)") (class "Default")
      (node (ref "R64") (pin "2") (pinfunction "2_2") (pintype "passive"))
      (node (ref "U30") (pin "6") (pinfunction "RDT_6") (pintype "input"))
    )
    (net (code "81") (name "Net-(U31-1IN+)") (class "Default")
      (node (ref "C124") (pin "2") (pinfunction "2_2") (pintype "passive"))
      (node (ref "C169") (pin "2") (pinfunction "2_2") (pintype "passive"))
      (node (ref "R179") (pin "1") (pinfunction "1_1") (pintype "passive"))
      (node (ref "U31") (pin "1") (pinfunction "1IN+_1") (pintype "input"))
      (node (ref "U31") (pin "13") (pinfunction "OUTPUT_CTRL_13") (pintype "input"))
      (node (ref "U31") (pin "16") (pinfunction "2IN+_16") (pintype "input"))
      (node (ref "U31") (pin "4") (pinfunction "DTC_4") (pintype "input"))
      (node (ref "U31") (pin "7") (pinfunction "GND_7") (pintype "power_in"))
    )
    (net (code "82") (name "Net-(U31-1IN-)") (class "Default")
      (node (ref "C101") (pin "1") (pinfunction "1_1") (pintype "passive"))
      (node (ref "R92") (pin "1") (pinfunction "1_1") (pintype "passive"))
      (node (ref "U31") (pin "14") (pinfunction "REF_14") (pintype "output"))
      (node (ref "U31") (pin "15") (pinfunction "2IN-_15") (pintype "input"))
      (node (ref "U31") (pin "2") (pinfunction "1IN-_2") (pintype "input"))
    )
    (net (code "83") (name "Net-(U31-CT)") (class "Default")
      (node (ref "C124") (pin "1") (pinfunction "1_1") (pintype "passive"))
      (node (ref "U31") (pin "5") (pinfunction "CT_5") (pintype "passive"))
    )
    (net (code "84") (name "Net-(U31-FEEDBACK)") (class "Default")
      (node (ref "R28") (pin "2") (pinfunction "2_2") (pintype "passive"))
      (node (ref "U31") (pin "3") (pinfunction "FEEDBACK_3") (pintype "input"))
    )
    (net (code "85") (name "Net-(U31-RT)") (class "Default")
      (node (ref "R179") (pin "2") (pinfunction "2_2") (pintype "passive"))
      (node (ref "U31") (pin "6") (pinfunction "RT_6") (pintype "passive"))
    )
    (net (code "86") (name "Net-(U31-VCC)") (class "Default")
      (node (ref "C169") (pin "1") (pinfunction "1_1") (pintype "passive"))
      (node (ref "R174") (pin "2") (pinfunction "2_2") (pintype "passive"))
      (node (ref "U31") (pin "12") (pinfunction "VCC_12") (pintype "power_in"))
    )
    (net (code "87") (name "Net-(U32-OUT)") (class "Default")
      (node (ref "R42") (pin "2") (pinfunction "2_2") (pintype "passive"))
      (node (ref "U32") (pin "9") (pinfunction "OUT_9") (pintype "output"))
    )
    (net (code "88") (name "Net-(U32-SEN)") (class "Default")
      (node (ref "R39") (pin "1") (pinfunction "1_1") (pintype "passive"))
      (node (ref "U32") (pin "1") (pinfunction "SEN_1") (pintype "input"))
    )
    (net (code "89") (name "Net-(U32-TIMER)") (class "Default")
      (node (ref "C98") (pin "2") (pinfunction "2_2") (pintype "passive"))
      (node (ref "U32") (pin "7") (pinfunction "TIMER_7") (pintype "input"))
    )
    (net (code "90") (name "Net-(U32-nPGD)") (class "Default")
      (node (ref "R158") (pin "2") (pinfunction "2_2") (pintype "passive"))
      (node (ref "U32") (pin "8") (pinfunction "nPGD_8") (pintype "open_collector"))
    )
    (net (code "91") (name "Net-(U33A-IN_A+)") (class "Default")
      (node (ref "R166") (pin "1") (pinfunction "1_1") (pintype "passive"))
      (node (ref "R167") (pin "2") (pinfunction "2_2") (pintype "passive"))
      (node (ref "U33") (pin "3") (pinfunction "IN_A+_3") (pintype "input"))
    )
    (net (code "92") (name "Net-(U33A-IN_A-)") (class "Default")
      (node (ref "C183") (pin "2") (pinfunction "2_2") (pintype "passive"))
      (node (ref "R178") (pin "2") (pinfunction "2_2") (pintype "passive"))
      (node (ref "R185") (pin "1") (pinfunction "1_1") (pintype "passive"))
      (node (ref "U33") (pin "2") (pinfunction "IN_A-_2") (pintype "input"))
    )
    (net (code "93") (name "Net-(U33A-V+)") (class "Default")
      (node (ref "C99") (pin "1") (pinfunction "1_1") (pintype "passive"))
      (node (ref "R155") (pin "2") (pinfunction "2_2") (pintype "passive"))
      (node (ref "U33") (pin "8") (pinfunction "V+_8") (pintype "power_in"))
    )
    (net (code "94") (name "Net-(U33B-IN_B+)") (class "Default")
      (node (ref "C95") (pin "2") (pinfunction "2_2") (pintype "passive"))
      (node (ref "R93") (pin "2") (pinfunction "2_2") (pintype "passive"))
      (node (ref "U33") (pin "5") (pinfunction "IN_B+_5") (pintype "input"))
    )
    (net (code "95") (name "Net-(U33B-IN_B-)") (class "Default")
      (node (ref "C118") (pin "2") (pinfunction "2_2") (pintype "passive"))
      (node (ref "C170") (pin "2") (pinfunction "2_2") (pintype "passive"))
      (node (ref "C90") (pin "2") (pinfunction "2_2") (pintype "passive"))
      (node (ref "R176") (pin "1") (pinfunction "1_1") (pintype "passive"))
      (node (ref "R96") (pin "2") (pinfunction "2_2") (pintype "passive"))
      (node (ref "U33") (pin "6") (pinfunction "IN_B-_6") (pintype "input"))
    )
    (net (code "96") (name "PGND") (class "Default")
      (node (ref "C10") (pin "2") (pinfunction "-_2") (pintype "passive"))
      (node (ref "C11") (pin "2") (pinfunction "2_2") (pintype "passive"))
      (node (ref "C12") (pin "2") (pinfunction "2_2") (pintype "passive"))
      (node (ref "C166") (pin "1") (pinfunction "1_1") (pintype "passive"))
      (node (ref "C168") (pin "1") (pinfunction "1_1") (pintype "passive"))
      (node (ref "C17") (pin "2") (pinfunction "2_2") (pintype "passive"))
      (node (ref "C171") (pin "2") (pinfunction "2_2") (pintype "passive"))
      (node (ref "C177") (pin "1") (pinfunction "1_1") (pintype "passive"))
      (node (ref "C20") (pin "2") (pinfunction "2_2") (pintype "passive"))
      (node (ref "C24") (pin "2") (pinfunction "-_2") (pintype "passive"))
      (node (ref "C74") (pin "2") (pinfunction "2_2") (pintype "passive"))
      (node (ref "C87") (pin "1") (pinfunction "1_1") (pintype "passive"))
      (node (ref "C97") (pin "2") (pinfunction "2_2") (pintype "passive"))
      (node (ref "C98") (pin "1") (pinfunction "1_1") (pintype "passive"))
      (node (ref "D15") (pin "2") (pinfunction "A_2") (pintype "passive"))
      (node (ref "D7") (pin "2") (pinfunction "A_2") (pintype "passive"))
      (node (ref "Q10") (pin "2") (pinfunction "S_2") (pintype "passive"))
      (node (ref "Q9") (pin "1") (pinfunction "S_1") (pintype "passive"))
      (node (ref "Q9") (pin "2") (pinfunction "S_2") (pintype "passive"))
      (node (ref "Q9") (pin "3") (pinfunction "S_3") (pintype "passive"))
      (node (ref "R177") (pin "1") (pinfunction "1_1") (pintype "passive"))
      (node (ref "R34") (pin "2") (pinfunction "2_2") (pintype "passive"))
      (node (ref "R43") (pin "1") (pinfunction "1_1") (pintype "passive"))
      (node (ref "R64") (pin "1") (pinfunction "1_1") (pintype "passive"))
      (node (ref "R65") (pin "2") (pinfunction "2_2") (pintype "passive"))
      (node (ref "R66") (pin "2") (pinfunction "2_2") (pintype "passive"))
      (node (ref "R75") (pin "1") (pinfunction "1_1") (pintype "passive"))
      (node (ref "R8") (pin "1") (pinfunction "1_1") (pintype "passive"))
      (node (ref "U30") (pin "9") (pinfunction "VSS_9") (pintype "power_in"))
      (node (ref "U32") (pin "6") (pinfunction "GND_6") (pintype "power_in"))
    )
    (net (code "97") (name "unconnected-(C101-Pad2)") (class "Default")
      (node (ref "C101") (pin "2") (pinfunction "2_2") (pintype "passive"))
    )
    (net (code "98") (name "unconnected-(U15B-V+-Pad8)") (class "Default")
      (node (ref "U15") (pin "8") (pinfunction "V+_8") (pintype "power_in"))
    )
    (net (code "99") (name "unconnected-(U15B-V--Pad4)") (class "Default")
      (node (ref "U15") (pin "4") (pinfunction "V-_4") (pintype "power_in"))
    )
    (net (code "100") (name "unconnected-(U19-VSS-Pad3)") (class "Default")
      (node (ref "U19") (pin "3") (pinfunction "VSS_3") (pintype "power_in"))
    )
    (net (code "101") (name "unconnected-(U30-NC-Pad5)") (class "Default")
      (node (ref "U30") (pin "5") (pinfunction "NC_5") (pintype "passive"))
    )
    (net (code "102") (name "unconnected-(U31-C1-Pad8)") (class "Default")
      (node (ref "U31") (pin "8") (pinfunction "C1_8") (pintype "passive+no_connect"))
    )
    (net (code "103") (name "unconnected-(U33B-V+-Pad8)") (class "Default")
      (node (ref "U33") (pin "8") (pinfunction "V+_8") (pintype "power_in"))
    )
    (net (code "104") (name "unconnected-(U33B-V--Pad4)") (class "Default")
      (node (ref "U33") (pin "4") (pinfunction "V-_4") (pintype "power_in"))
    )
  )
)
